# EEZ_DIB_AFE1_r1B5.net
KiCad netlist of a schematic drawn in EAGLE
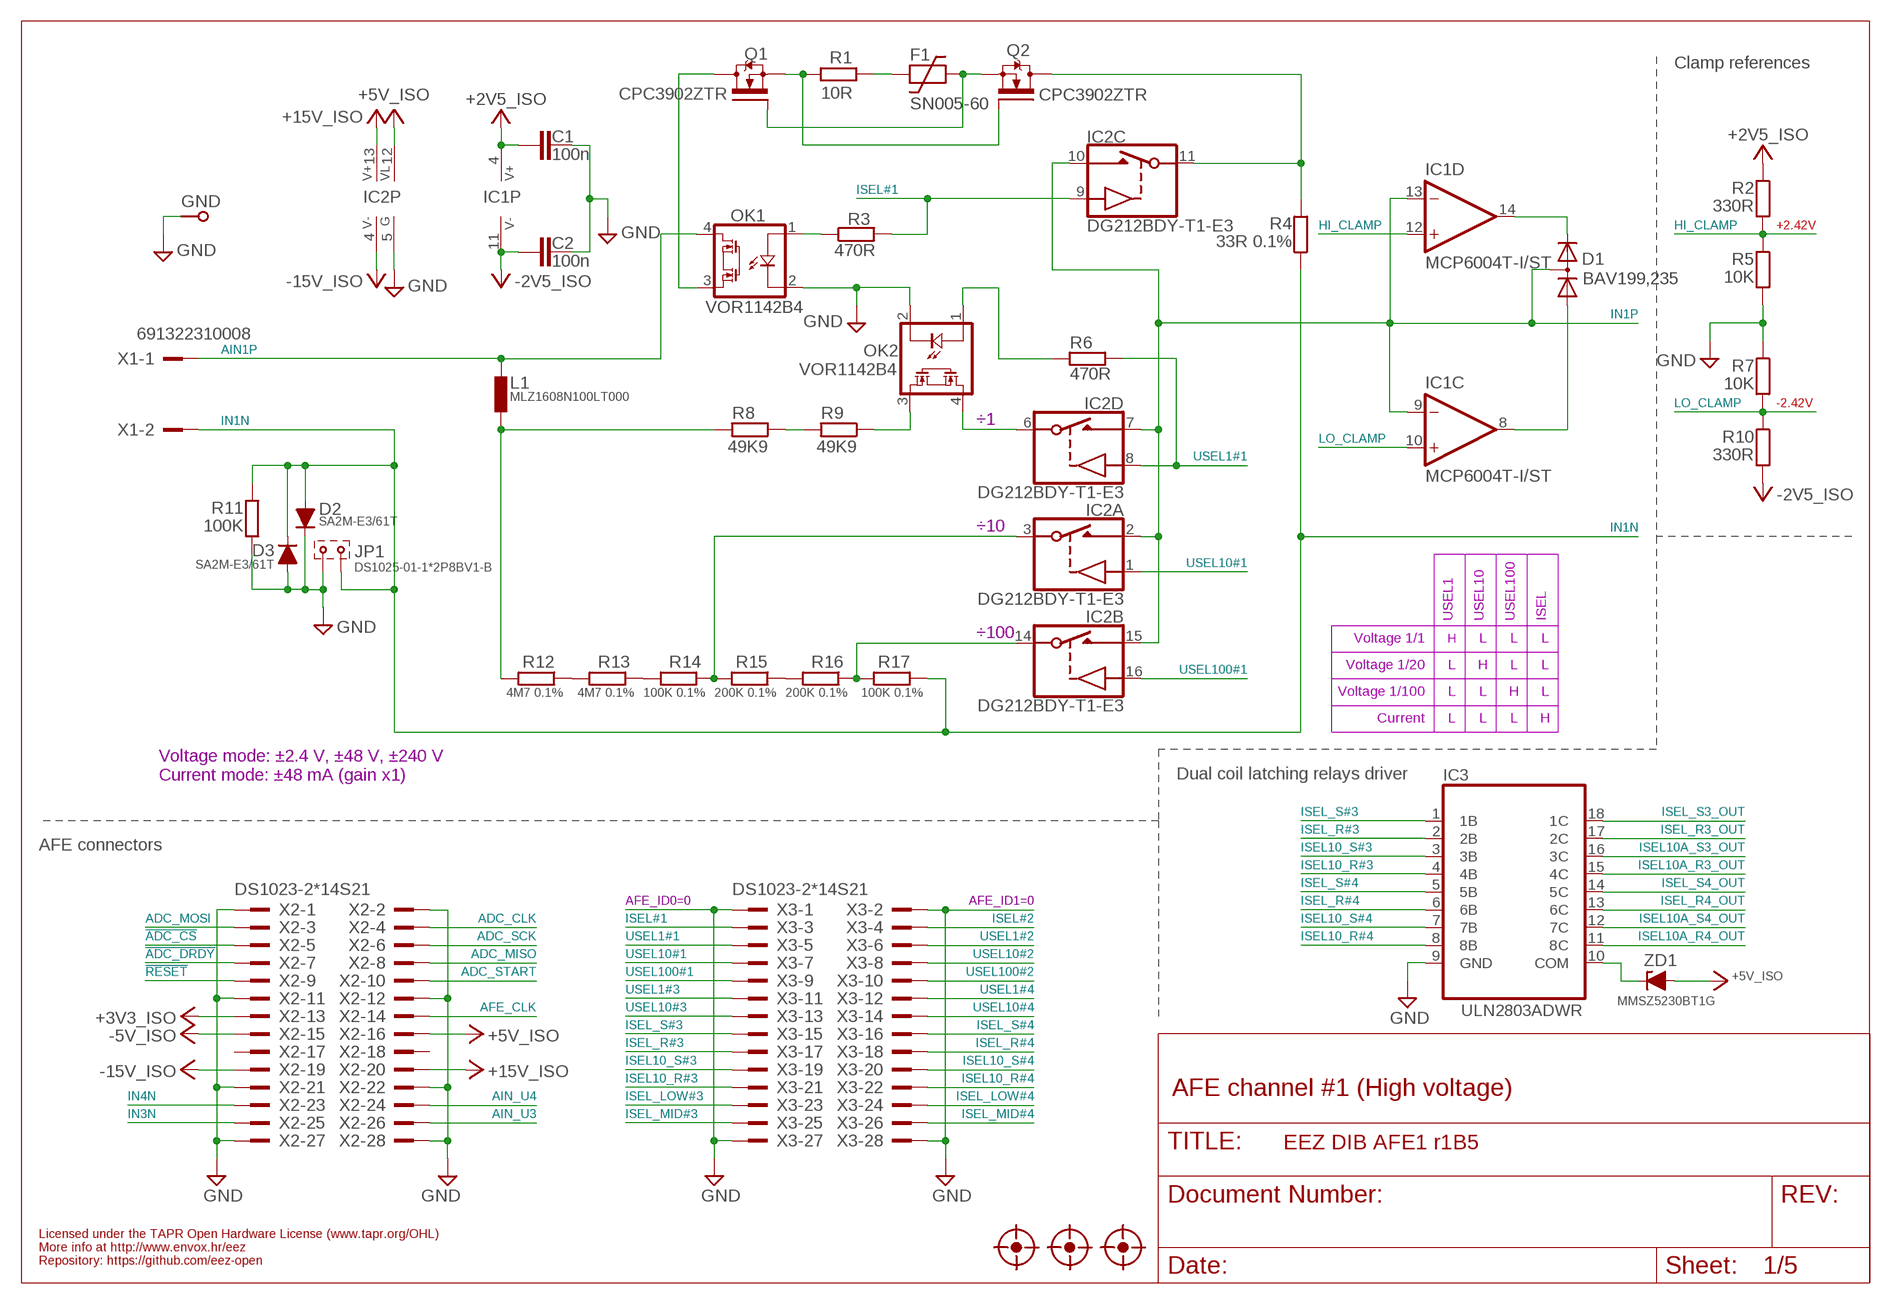
[diagram p0: schematic, sheet 1]
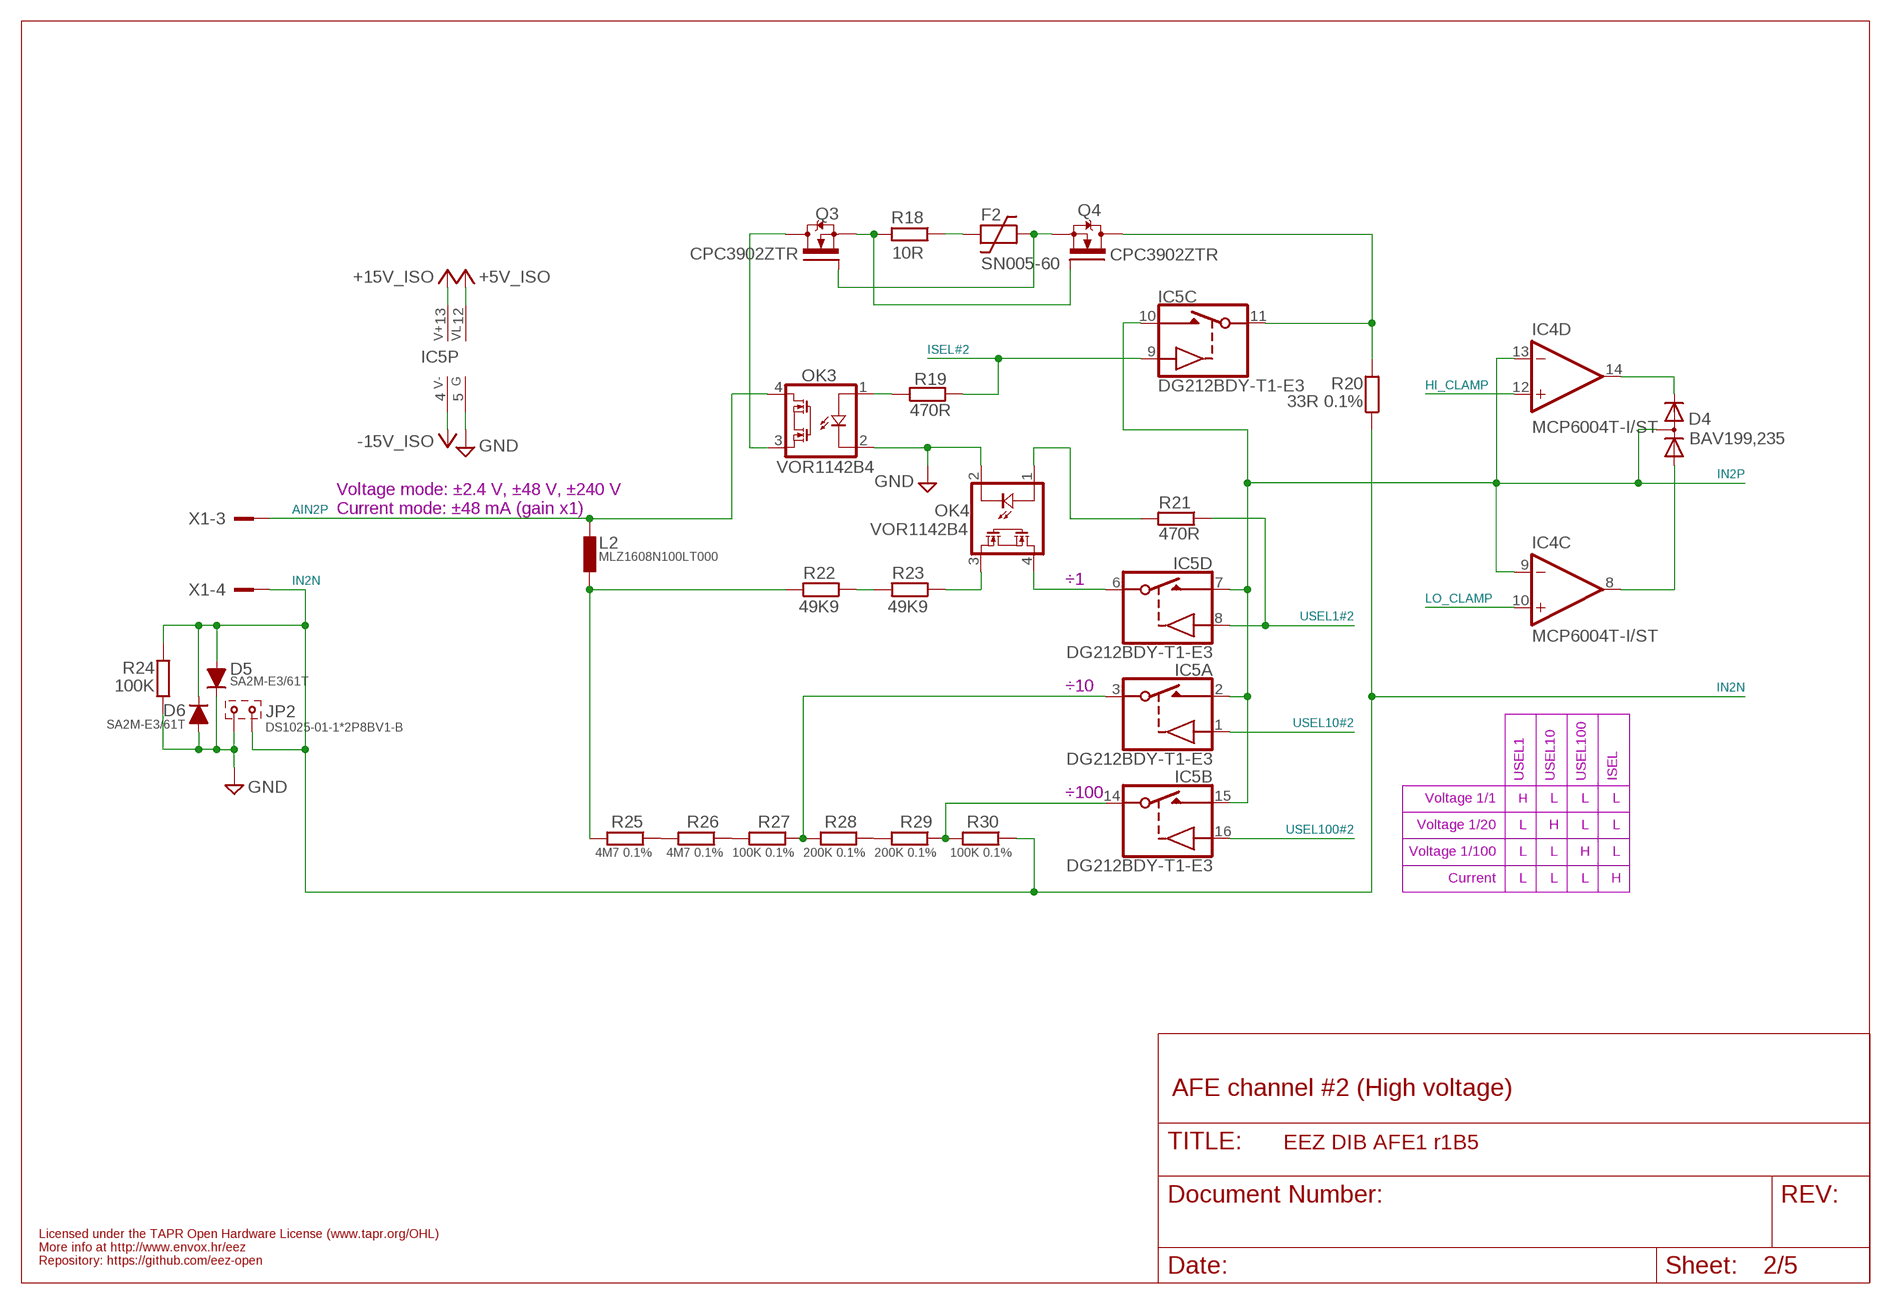
[diagram p1: schematic, sheet 2]
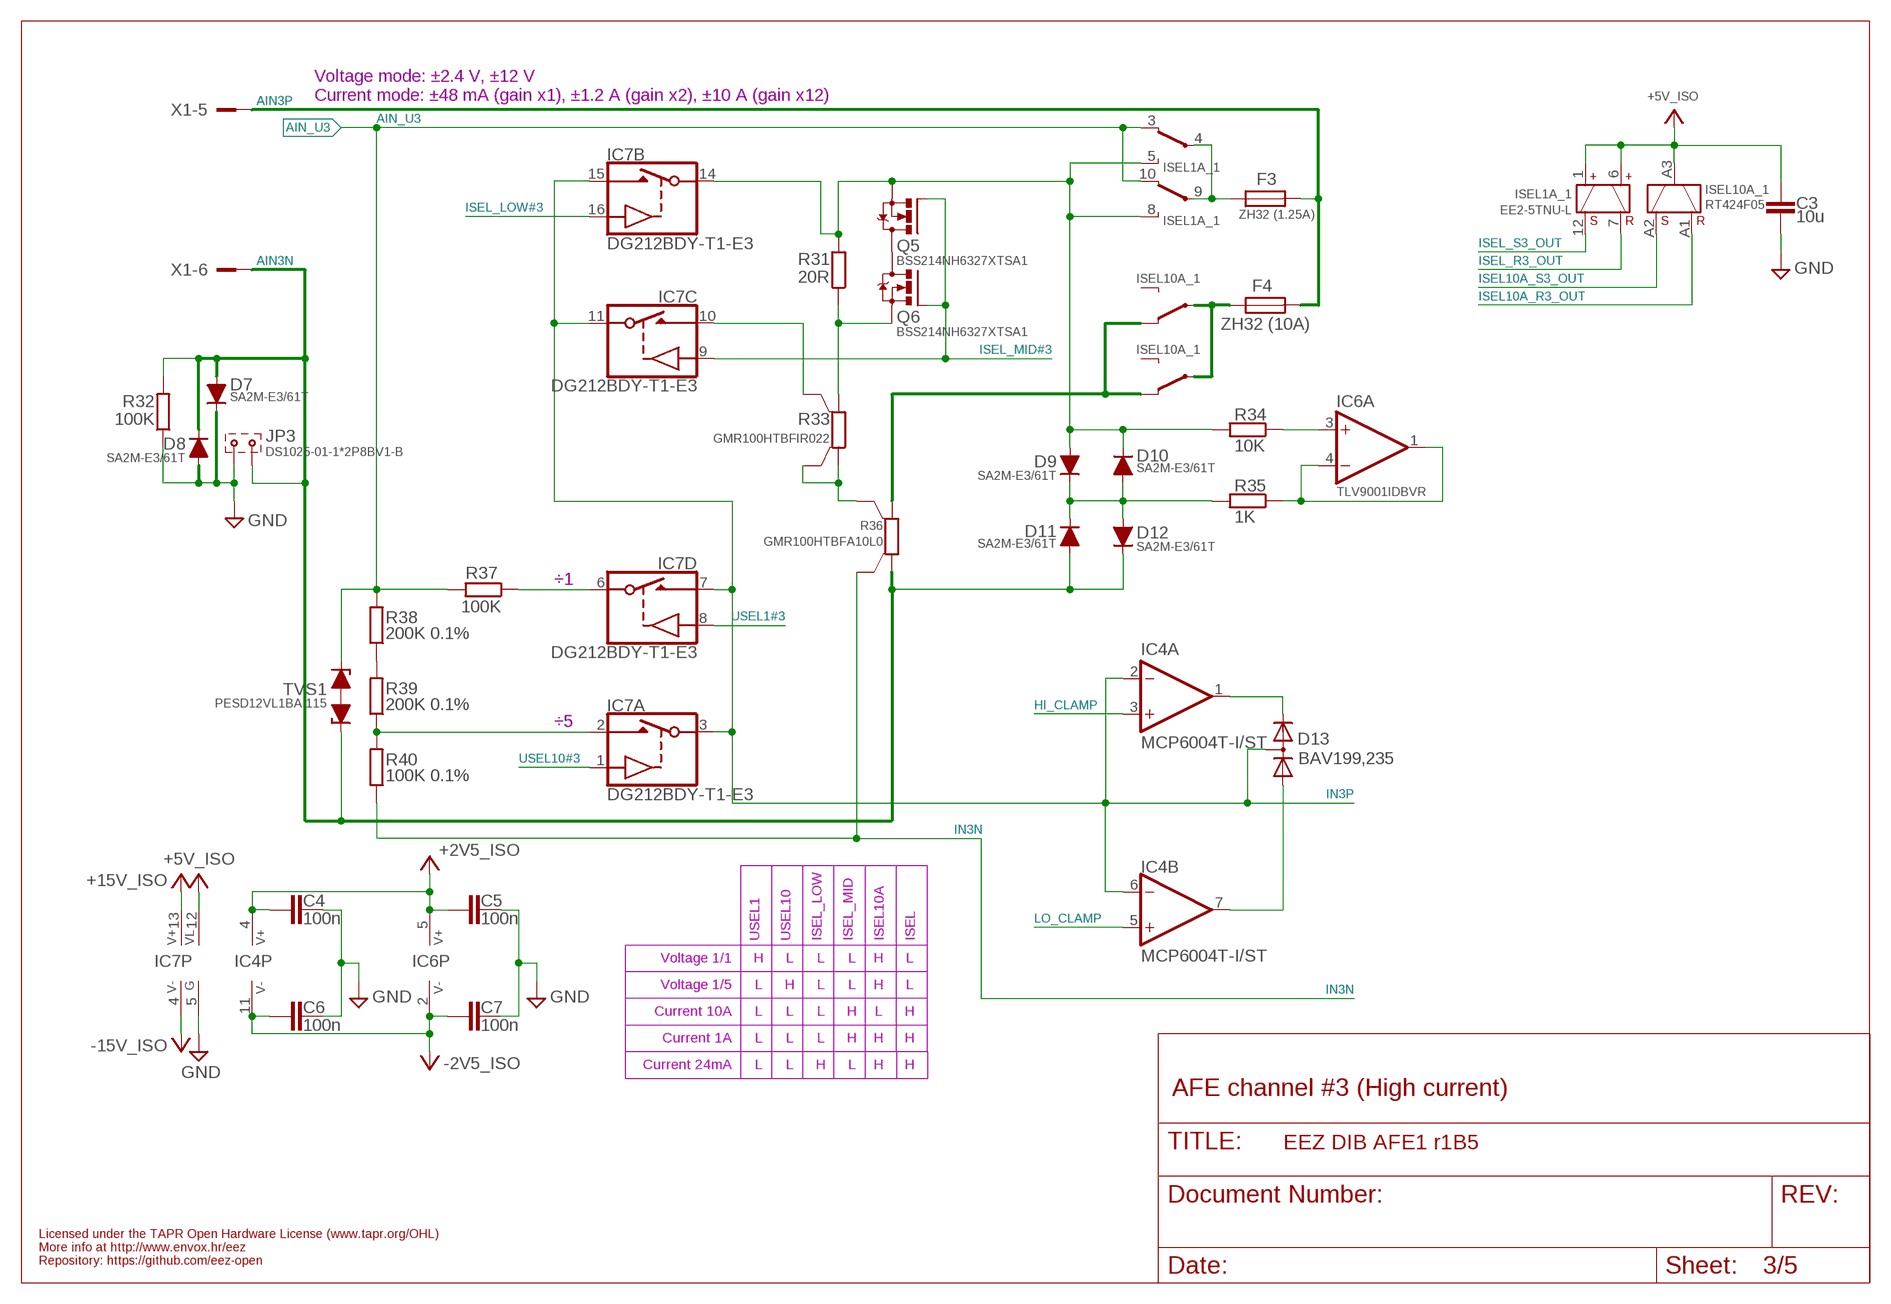
[diagram p2: schematic, sheet 3]
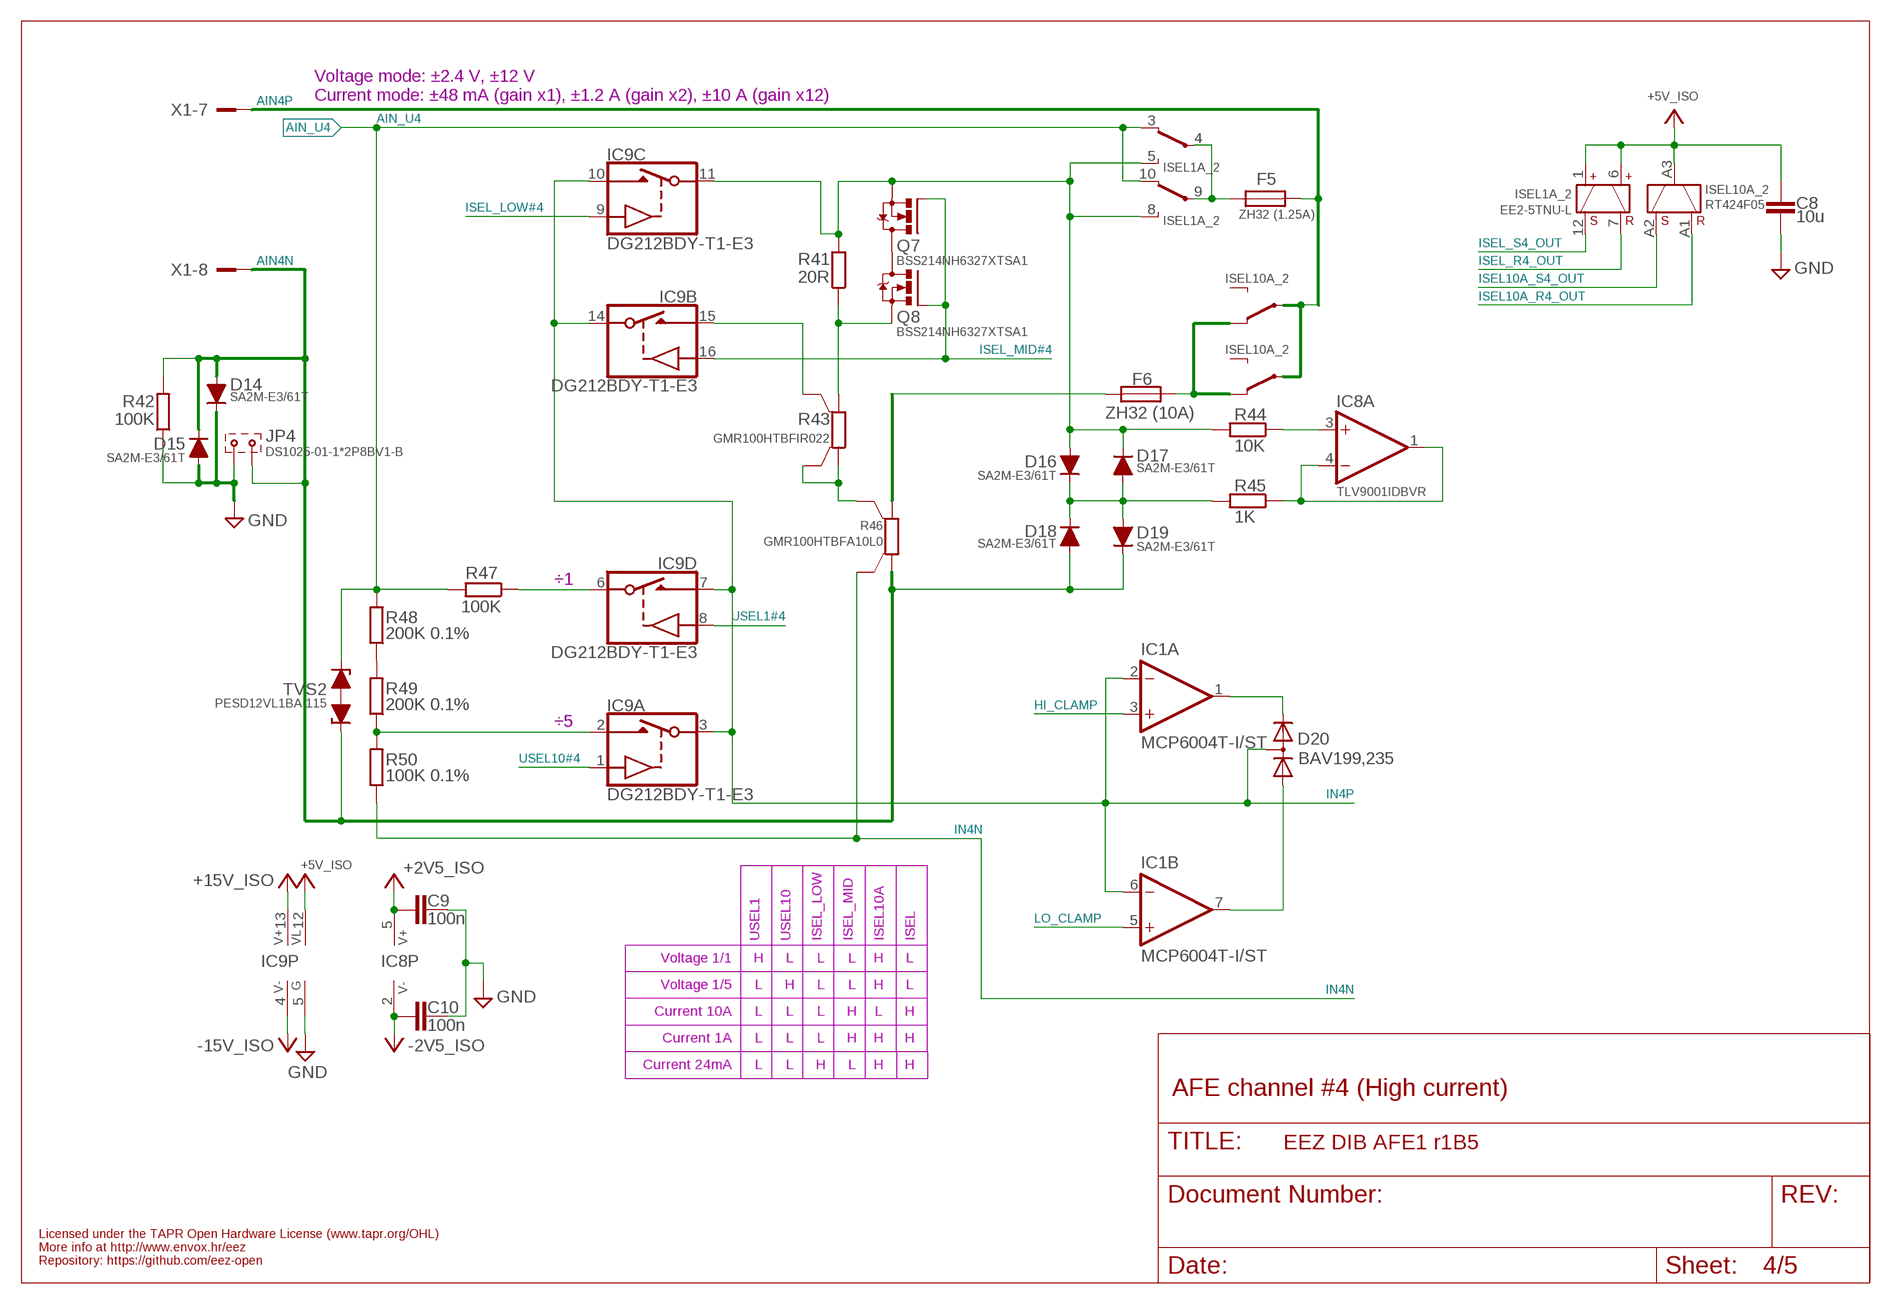
[diagram p3: schematic, sheet 4]
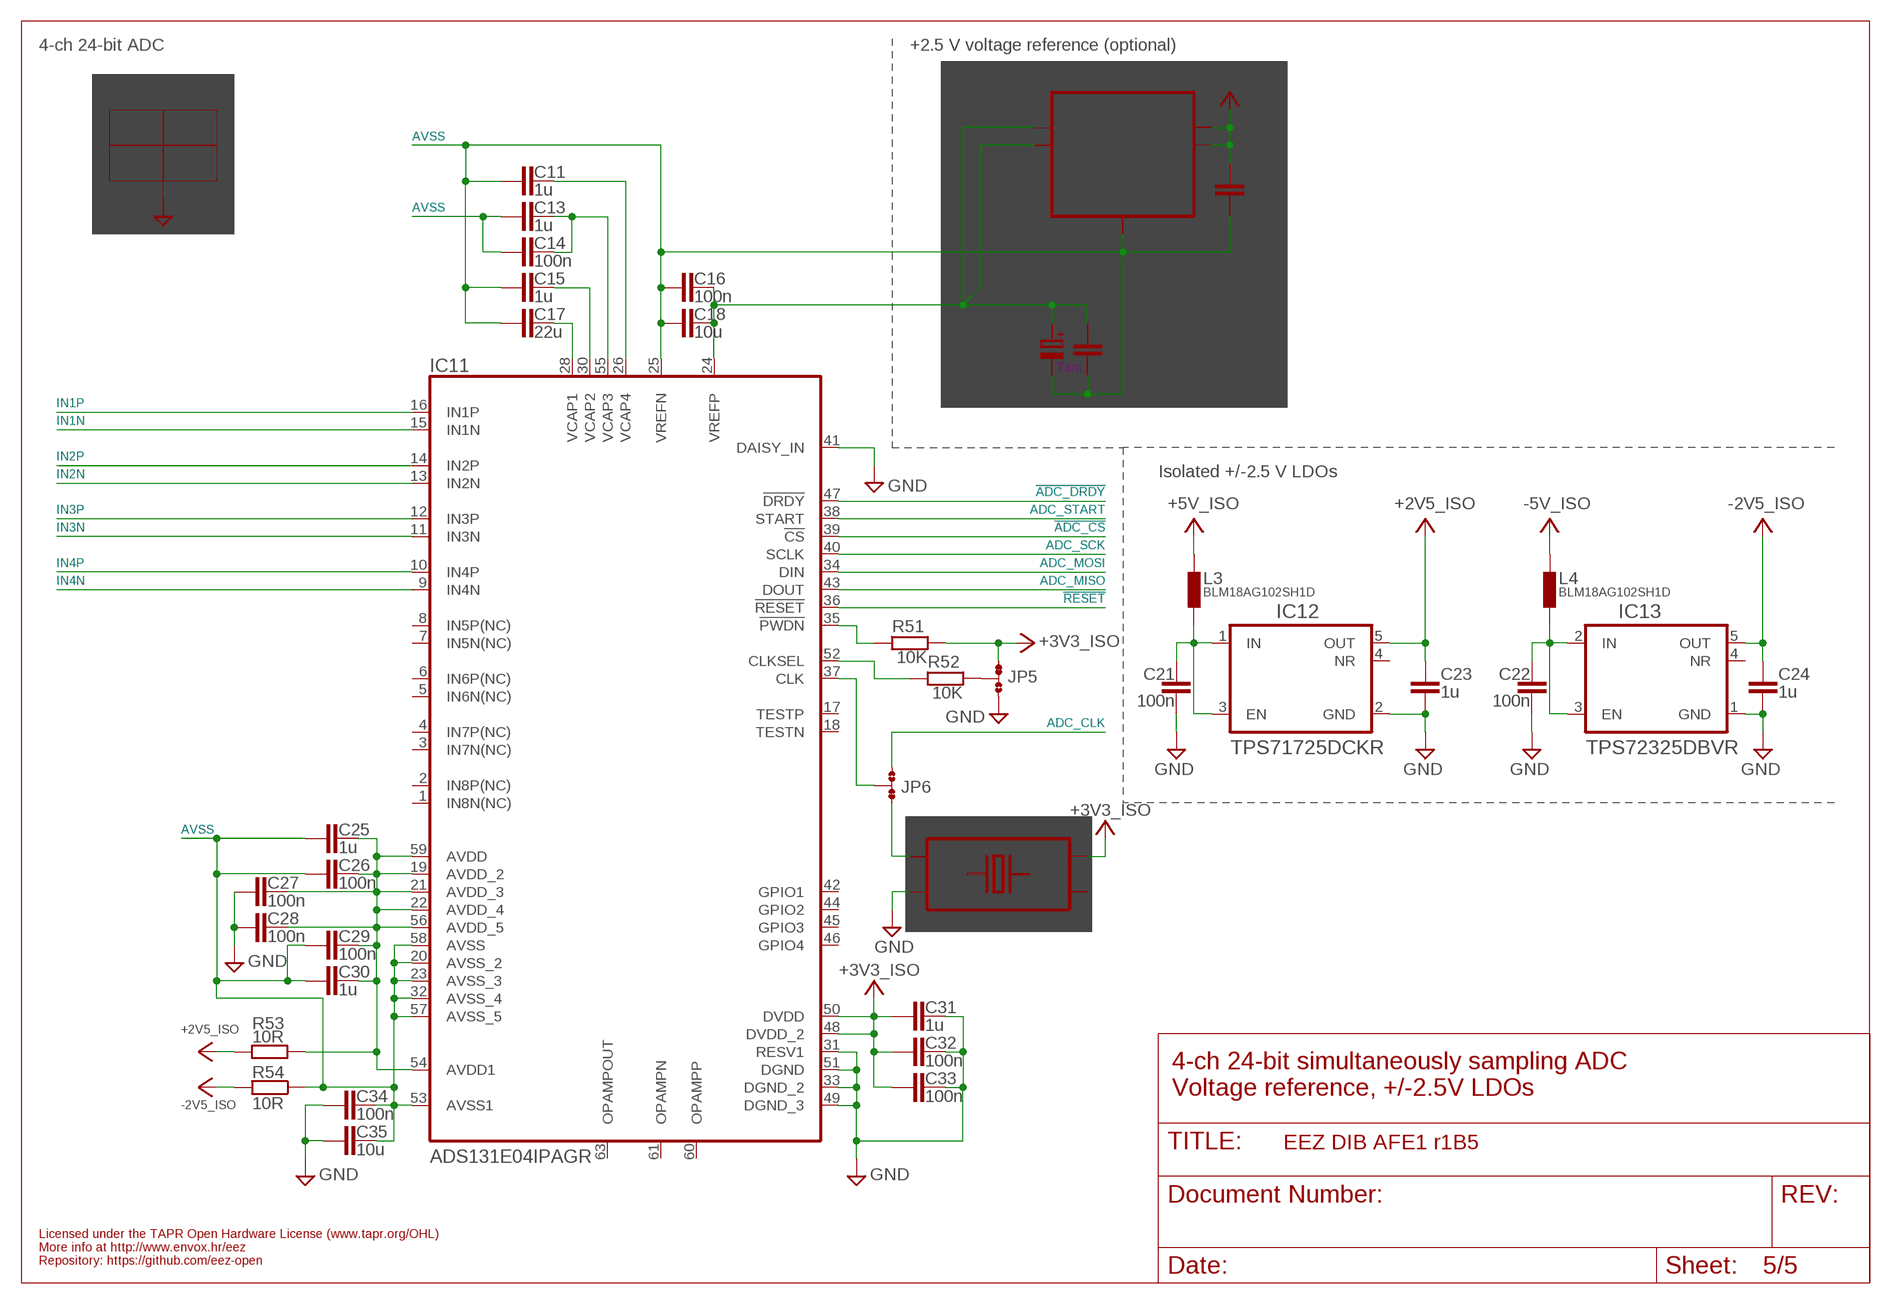
[diagram p4: schematic, sheet 5]

(export (version "E")
  (design (tool "Eeschema 10.0.6"))
  (components
    (comp (ref "D4")
      (value "BAV199,235")
      (footprint "eagle-import:SOT23")
      (libsource (lib "eagle-import") (part "BAV199"))
    )
    (comp (ref "D5")
      (value "SA2M-E3/61T")
      (footprint "eagle-import:SMA_NARROW")
      (libsource (lib "eagle-import") (part "DIODE_SMA-NARROW"))
    )
    (comp (ref "D6")
      (value "SA2M-E3/61T")
      (footprint "eagle-import:SMA_NARROW")
      (libsource (lib "eagle-import") (part "DIODE_SMA-NARROW"))
    )
    (comp (ref "F2")
      (value "SN005-60")
      (footprint "eagle-import:C1206-HV")
      (libsource (lib "eagle-import") (part "FUSE_RESETTABLE2"))
    )
    (comp (ref "IC4")
      (value "MCP6004T-I/ST")
      (footprint "eagle-import:PW(R-PDSO-G14)")
      (libsource (lib "eagle-import") (part "OPA4197PW"))
    )
    (comp (ref "IC5")
      (value "DG212BDY-T1-E3")
      (footprint "eagle-import:SO16")
      (libsource (lib "eagle-import") (part "DG212BDY-T1-E3"))
    )
    (comp (ref "JP2")
      (value "DS1025-01-1*2P8BV1-B")
      (footprint "eagle-import:2MM-2")
      (libsource (lib "eagle-import") (part "JUMPER-2PIN-2MM"))
    )
    (comp (ref "L2")
      (value "MLZ1608N100LT000")
      (footprint "eagle-import:BEAD0603")
      (libsource (lib "eagle-import") (part "FERRITE_BEAD0603"))
    )
    (comp (ref "OK3")
      (value "VOR1142B4")
      (footprint "eagle-import:DIL4-SMD")
      (libsource (lib "eagle-import") (part "VOR1142B4"))
    )
    (comp (ref "OK4")
      (value "VOR1142B4")
      (footprint "eagle-import:DIL4-SMD")
      (libsource (lib "eagle-import") (part "VOR1142B4"))
    )
    (comp (ref "Q3")
      (value "CPC3902ZTR")
      (footprint "eagle-import:SOT230P700X180-4N")
      (libsource (lib "eagle-import") (part "BSP129SOT-223"))
    )
    (comp (ref "Q4")
      (value "CPC3902ZTR")
      (footprint "eagle-import:SOT230P700X180-4N")
      (libsource (lib "eagle-import") (part "BSP129SOT-223"))
    )
    (comp (ref "R18")
      (value "10R")
      (footprint "eagle-import:R0805")
      (libsource (lib "eagle-import") (part "R-EU_R0805"))
    )
    (comp (ref "R19")
      (value "470R")
      (footprint "eagle-import:R0805")
      (libsource (lib "eagle-import") (part "R-EU_R0805"))
    )
    (comp (ref "R20")
      (value "33R 0.1%")
      (footprint "eagle-import:R1206")
      (libsource (lib "eagle-import") (part "R-EU_R1206"))
    )
    (comp (ref "R21")
      (value "470R")
      (footprint "eagle-import:R0805")
      (libsource (lib "eagle-import") (part "R-EU_R0805"))
    )
    (comp (ref "R22")
      (value "49K9")
      (footprint "eagle-import:R1206")
      (libsource (lib "eagle-import") (part "R-EU_R1206"))
    )
    (comp (ref "R23")
      (value "49K9")
      (footprint "eagle-import:R1206")
      (libsource (lib "eagle-import") (part "R-EU_R1206"))
    )
    (comp (ref "R24")
      (value "100K")
      (footprint "eagle-import:R1206")
      (libsource (lib "eagle-import") (part "R-EU_R1206"))
    )
    (comp (ref "R25")
      (value "4M7 0.1%")
      (footprint "eagle-import:R1206")
      (libsource (lib "eagle-import") (part "R-EU_R1206"))
    )
    (comp (ref "R26")
      (value "4M7 0.1%")
      (footprint "eagle-import:R1206")
      (libsource (lib "eagle-import") (part "R-EU_R1206"))
    )
    (comp (ref "R27")
      (value "100K 0.1%")
      (footprint "eagle-import:R1206")
      (libsource (lib "eagle-import") (part "R-EU_R1206"))
    )
    (comp (ref "R28")
      (value "200K 0.1%")
      (footprint "eagle-import:R1206")
      (libsource (lib "eagle-import") (part "R-EU_R1206"))
    )
    (comp (ref "R29")
      (value "200K 0.1%")
      (footprint "eagle-import:R1206")
      (libsource (lib "eagle-import") (part "R-EU_R1206"))
    )
    (comp (ref "R30")
      (value "100K 0.1%")
      (footprint "eagle-import:R1206")
      (libsource (lib "eagle-import") (part "R-EU_R1206"))
    )
    (comp (ref "X1")
      (value "691322310008")
      (footprint "eagle-import:691322310008")
      (libsource (lib "eagle-import") (part "691322310008"))
    )
    (comp (ref "C1")
      (value "100n")
      (footprint "eagle-import:C0603")
      (libsource (lib "eagle-import") (part "C-EUC0603"))
    )
    (comp (ref "C2")
      (value "100n")
      (footprint "eagle-import:C0603")
      (libsource (lib "eagle-import") (part "C-EUC0603"))
    )
    (comp (ref "D1")
      (value "BAV199,235")
      (footprint "eagle-import:SOT23")
      (libsource (lib "eagle-import") (part "BAV199"))
    )
    (comp (ref "D2")
      (value "SA2M-E3/61T")
      (footprint "eagle-import:SMA_NARROW")
      (libsource (lib "eagle-import") (part "DIODE_SMA-NARROW"))
    )
    (comp (ref "D3")
      (value "SA2M-E3/61T")
      (footprint "eagle-import:SMA_NARROW")
      (libsource (lib "eagle-import") (part "DIODE_SMA-NARROW"))
    )
    (comp (ref "F1")
      (value "SN005-60")
      (footprint "eagle-import:C1206-HV")
      (libsource (lib "eagle-import") (part "FUSE_RESETTABLE2"))
    )
    (comp (ref "FM1")
      (value "FIDUCIAL_2")
      (footprint "eagle-import:FIDUCIAL_DUAL")
      (libsource (lib "eagle-import") (part "FIDUCIAL_2"))
    )
    (comp (ref "FM2")
      (value "FIDUCIAL_2")
      (footprint "eagle-import:FIDUCIAL_DUAL")
      (libsource (lib "eagle-import") (part "FIDUCIAL_2"))
    )
    (comp (ref "FM3")
      (value "FIDUCIAL_2")
      (footprint "eagle-import:FIDUCIAL_DUAL")
      (libsource (lib "eagle-import") (part "FIDUCIAL_2"))
    )
    (comp (ref "GND")
      (value "PCB_TEST_TABSHIELD")
      (footprint "eagle-import:PCB_SHIELD_TAB")
      (libsource (lib "eagle-import") (part "PCB_TEST_TABSHIELD"))
    )
    (comp (ref "IC1")
      (value "MCP6004T-I/ST")
      (footprint "eagle-import:PW(R-PDSO-G14)")
      (libsource (lib "eagle-import") (part "OPA4197PW"))
    )
    (comp (ref "IC2")
      (value "DG212BDY-T1-E3")
      (footprint "eagle-import:SO16")
      (libsource (lib "eagle-import") (part "DG212BDY-T1-E3"))
    )
    (comp (ref "IC3")
      (value "ULN2803ADWR")
      (footprint "eagle-import:DW18_TEX-M")
      (libsource (lib "eagle-import") (part "ULN2803ADWR"))
    )
    (comp (ref "JP1")
      (value "DS1025-01-1*2P8BV1-B")
      (footprint "eagle-import:2MM-2")
      (libsource (lib "eagle-import") (part "JUMPER-2PIN-2MM"))
    )
    (comp (ref "L1")
      (value "MLZ1608N100LT000")
      (footprint "eagle-import:BEAD0603")
      (libsource (lib "eagle-import") (part "FERRITE_BEAD0603"))
    )
    (comp (ref "OK1")
      (value "VOR1142B4")
      (footprint "eagle-import:DIL4-SMD")
      (libsource (lib "eagle-import") (part "VOR1142B4"))
    )
    (comp (ref "OK2")
      (value "VOR1142B4")
      (footprint "eagle-import:DIL4-SMD")
      (libsource (lib "eagle-import") (part "VOR1142B4"))
    )
    (comp (ref "Q1")
      (value "CPC3902ZTR")
      (footprint "eagle-import:SOT230P700X180-4N")
      (libsource (lib "eagle-import") (part "BSP129SOT-223"))
    )
    (comp (ref "Q2")
      (value "CPC3902ZTR")
      (footprint "eagle-import:SOT230P700X180-4N")
      (libsource (lib "eagle-import") (part "BSP129SOT-223"))
    )
    (comp (ref "R1")
      (value "10R")
      (footprint "eagle-import:R0805")
      (libsource (lib "eagle-import") (part "R-EU_R0805"))
    )
    (comp (ref "R2")
      (value "330R")
      (footprint "eagle-import:R0805")
      (libsource (lib "eagle-import") (part "R-EU_R0805"))
    )
    (comp (ref "R3")
      (value "470R")
      (footprint "eagle-import:R0805")
      (libsource (lib "eagle-import") (part "R-EU_R0805"))
    )
    (comp (ref "R4")
      (value "33R 0.1%")
      (footprint "eagle-import:R1206")
      (libsource (lib "eagle-import") (part "R-EU_R1206"))
    )
    (comp (ref "R5")
      (value "10K")
      (footprint "eagle-import:R0805")
      (libsource (lib "eagle-import") (part "R-EU_R0805"))
    )
    (comp (ref "R6")
      (value "470R")
      (footprint "eagle-import:R0805")
      (libsource (lib "eagle-import") (part "R-EU_R0805"))
    )
    (comp (ref "R7")
      (value "10K")
      (footprint "eagle-import:R0805")
      (libsource (lib "eagle-import") (part "R-EU_R0805"))
    )
    (comp (ref "R8")
      (value "49K9")
      (footprint "eagle-import:R1206")
      (libsource (lib "eagle-import") (part "R-EU_R1206"))
    )
    (comp (ref "R9")
      (value "49K9")
      (footprint "eagle-import:R1206")
      (libsource (lib "eagle-import") (part "R-EU_R1206"))
    )
    (comp (ref "R10")
      (value "330R")
      (footprint "eagle-import:R0805")
      (libsource (lib "eagle-import") (part "R-EU_R0805"))
    )
    (comp (ref "R11")
      (value "100K")
      (footprint "eagle-import:R1206")
      (libsource (lib "eagle-import") (part "R-EU_R1206"))
    )
    (comp (ref "R12")
      (value "4M7 0.1%")
      (footprint "eagle-import:R1206")
      (libsource (lib "eagle-import") (part "R-EU_R1206"))
    )
    (comp (ref "R13")
      (value "4M7 0.1%")
      (footprint "eagle-import:R1206")
      (libsource (lib "eagle-import") (part "R-EU_R1206"))
    )
    (comp (ref "R14")
      (value "100K 0.1%")
      (footprint "eagle-import:R1206")
      (libsource (lib "eagle-import") (part "R-EU_R1206"))
    )
    (comp (ref "R15")
      (value "200K 0.1%")
      (footprint "eagle-import:R1206")
      (libsource (lib "eagle-import") (part "R-EU_R1206"))
    )
    (comp (ref "R16")
      (value "200K 0.1%")
      (footprint "eagle-import:R1206")
      (libsource (lib "eagle-import") (part "R-EU_R1206"))
    )
    (comp (ref "R17")
      (value "100K 0.1%")
      (footprint "eagle-import:R1206")
      (libsource (lib "eagle-import") (part "R-EU_R1206"))
    )
    (comp (ref "X2")
      (value "DS1023-2*14S21")
      (footprint "eagle-import:TSW-114-07-F-D")
      (libsource (lib "eagle-import") (part "TSW-114-07-F-D"))
    )
    (comp (ref "X3")
      (value "DS1023-2*14S21")
      (footprint "eagle-import:TSW-114-07-F-D")
      (libsource (lib "eagle-import") (part "TSW-114-07-F-D"))
    )
    (comp (ref "ZD1")
      (value "MMSZ5230BT1G")
      (footprint "eagle-import:SOD123")
      (libsource (lib "eagle-import") (part "ZENER-DIODESOD123"))
    )
    (comp (ref "C11")
      (value "1u")
      (footprint "eagle-import:C0805")
      (libsource (lib "eagle-import") (part "C-EUC0805"))
    )
    (comp (ref "C12")
      (value "N.C.")
      (footprint "eagle-import:C1206")
      (libsource (lib "eagle-import") (part "C-EUC1206"))
    )
    (comp (ref "C13")
      (value "1u")
      (footprint "eagle-import:C0805")
      (libsource (lib "eagle-import") (part "C-EUC0805"))
    )
    (comp (ref "C14")
      (value "100n")
      (footprint "eagle-import:C0603")
      (libsource (lib "eagle-import") (part "C-EUC0603"))
    )
    (comp (ref "C15")
      (value "1u")
      (footprint "eagle-import:C0805")
      (libsource (lib "eagle-import") (part "C-EUC0805"))
    )
    (comp (ref "C16")
      (value "100n")
      (footprint "eagle-import:C0603")
      (libsource (lib "eagle-import") (part "C-EUC0603"))
    )
    (comp (ref "C17")
      (value "22u")
      (footprint "eagle-import:C1206")
      (libsource (lib "eagle-import") (part "C-EUC1206"))
    )
    (comp (ref "C18")
      (value "10u")
      (footprint "eagle-import:C1206")
      (libsource (lib "eagle-import") (part "C-EUC1206"))
    )
    (comp (ref "C19")
      (value "N.C.")
      (footprint "eagle-import:EC1206")
      (libsource (lib "eagle-import") (part "ECAP1206"))
    )
    (comp (ref "C20")
      (value "N.C.")
      (footprint "eagle-import:C050-075X110")
      (libsource (lib "eagle-import") (part "C-EU7.5X11"))
    )
    (comp (ref "C21")
      (value "100n")
      (footprint "eagle-import:C0603")
      (libsource (lib "eagle-import") (part "C-EUC0603"))
    )
    (comp (ref "C22")
      (value "100n")
      (footprint "eagle-import:C0603")
      (libsource (lib "eagle-import") (part "C-EUC0603"))
    )
    (comp (ref "C23")
      (value "1u")
      (footprint "eagle-import:C0805")
      (libsource (lib "eagle-import") (part "C-EUC0805"))
    )
    (comp (ref "C24")
      (value "1u")
      (footprint "eagle-import:C0805")
      (libsource (lib "eagle-import") (part "C-EUC0805"))
    )
    (comp (ref "C25")
      (value "1u")
      (footprint "eagle-import:C0805")
      (libsource (lib "eagle-import") (part "C-EUC0805"))
    )
    (comp (ref "C26")
      (value "100n")
      (footprint "eagle-import:C0603")
      (libsource (lib "eagle-import") (part "C-EUC0603"))
    )
    (comp (ref "C27")
      (value "100n")
      (footprint "eagle-import:C0603")
      (libsource (lib "eagle-import") (part "C-EUC0603"))
    )
    (comp (ref "C28")
      (value "100n")
      (footprint "eagle-import:C0603")
      (libsource (lib "eagle-import") (part "C-EUC0603"))
    )
    (comp (ref "C29")
      (value "100n")
      (footprint "eagle-import:C0603")
      (libsource (lib "eagle-import") (part "C-EUC0603"))
    )
    (comp (ref "C30")
      (value "1u")
      (footprint "eagle-import:C0805")
      (libsource (lib "eagle-import") (part "C-EUC0805"))
    )
    (comp (ref "C31")
      (value "1u")
      (footprint "eagle-import:C0805")
      (libsource (lib "eagle-import") (part "C-EUC0805"))
    )
    (comp (ref "C32")
      (value "100n")
      (footprint "eagle-import:C0603")
      (libsource (lib "eagle-import") (part "C-EUC0603"))
    )
    (comp (ref "C33")
      (value "100n")
      (footprint "eagle-import:C0603")
      (libsource (lib "eagle-import") (part "C-EUC0603"))
    )
    (comp (ref "C34")
      (value "100n")
      (footprint "eagle-import:C0603")
      (libsource (lib "eagle-import") (part "C-EUC0603"))
    )
    (comp (ref "C35")
      (value "10u")
      (footprint "eagle-import:C1206")
      (libsource (lib "eagle-import") (part "C-EUC1206"))
    )
    (comp (ref "IC10")
      (value "N.C.")
      (footprint "eagle-import:MSOP-8_MS_LIT")
      (libsource (lib "eagle-import") (part "LTC6655BHMS8"))
    )
    (comp (ref "IC11")
      (value "ADS131E04IPAGR")
      (footprint "eagle-import:PAG64")
      (libsource (lib "eagle-import") (part "ADS131E0XIPAG"))
    )
    (comp (ref "IC12")
      (value "TPS71725DCKR")
      (footprint "eagle-import:DCK5")
      (libsource (lib "eagle-import") (part "TPS71725DCKR"))
    )
    (comp (ref "IC13")
      (value "TPS72325DBVR")
      (footprint "eagle-import:DBV5")
      (libsource (lib "eagle-import") (part "TPS72325DBVR"))
    )
    (comp (ref "JP5")
      (value "JP3-CUT-0805-ROTATED")
      (footprint "eagle-import:JP3-0805-CUT2")
      (libsource (lib "eagle-import") (part "JP3-CUT-0805-ROTATED"))
    )
    (comp (ref "JP6")
      (value "JP3-CUT-0805-ROTATED")
      (footprint "eagle-import:JP3-0805-CUT2")
      (libsource (lib "eagle-import") (part "JP3-CUT-0805-ROTATED"))
    )
    (comp (ref "L3")
      (value "BLM18AG102SH1D")
      (footprint "eagle-import:BEAD0603")
      (libsource (lib "eagle-import") (part "FERRITE_BEAD0603"))
    )
    (comp (ref "L4")
      (value "BLM18AG102SH1D")
      (footprint "eagle-import:BEAD0603")
      (libsource (lib "eagle-import") (part "FERRITE_BEAD0603"))
    )
    (comp (ref "R51")
      (value "10K")
      (footprint "eagle-import:R0805")
      (libsource (lib "eagle-import") (part "R-EU_R0805"))
    )
    (comp (ref "R52")
      (value "10K")
      (footprint "eagle-import:R0805")
      (libsource (lib "eagle-import") (part "R-EU_R0805"))
    )
    (comp (ref "R53")
      (value "10R")
      (footprint "eagle-import:R0805")
      (libsource (lib "eagle-import") (part "R-EU_R0805"))
    )
    (comp (ref "R54")
      (value "10R")
      (footprint "eagle-import:R0805")
      (libsource (lib "eagle-import") (part "R-EU_R0805"))
    )
    (comp (ref "S1")
      (value "N.C.")
      (footprint "eagle-import:2118732-2")
      (libsource (lib "eagle-import") (part "2118732-2"))
    )
    (comp (ref "XO1")
      (value "N.C.")
      (footprint "eagle-import:XLH")
      (libsource (lib "eagle-import") (part "XLH"))
    )
    (comp (ref "C3")
      (value "10u")
      (footprint "eagle-import:C1206")
      (libsource (lib "eagle-import") (part "C-EUC1206"))
    )
    (comp (ref "C4")
      (value "100n")
      (footprint "eagle-import:C0603")
      (libsource (lib "eagle-import") (part "C-EUC0603"))
    )
    (comp (ref "C5")
      (value "100n")
      (footprint "eagle-import:C0603")
      (libsource (lib "eagle-import") (part "C-EUC0603"))
    )
    (comp (ref "C6")
      (value "100n")
      (footprint "eagle-import:C0603")
      (libsource (lib "eagle-import") (part "C-EUC0603"))
    )
    (comp (ref "C7")
      (value "100n")
      (footprint "eagle-import:C0603")
      (libsource (lib "eagle-import") (part "C-EUC0603"))
    )
    (comp (ref "D7")
      (value "SA2M-E3/61T")
      (footprint "eagle-import:SMA_NARROW")
      (libsource (lib "eagle-import") (part "DIODE_SMA-NARROW"))
    )
    (comp (ref "D8")
      (value "SA2M-E3/61T")
      (footprint "eagle-import:SMA_NARROW")
      (libsource (lib "eagle-import") (part "DIODE_SMA-NARROW"))
    )
    (comp (ref "D9")
      (value "SA2M-E3/61T")
      (footprint "eagle-import:SMA_NARROW")
      (libsource (lib "eagle-import") (part "DIODE_SMA-NARROW"))
    )
    (comp (ref "D10")
      (value "SA2M-E3/61T")
      (footprint "eagle-import:SMA_NARROW")
      (libsource (lib "eagle-import") (part "DIODE_SMA-NARROW"))
    )
    (comp (ref "D11")
      (value "SA2M-E3/61T")
      (footprint "eagle-import:SMA_NARROW")
      (libsource (lib "eagle-import") (part "DIODE_SMA-NARROW"))
    )
    (comp (ref "D12")
      (value "SA2M-E3/61T")
      (footprint "eagle-import:SMA_NARROW")
      (libsource (lib "eagle-import") (part "DIODE_SMA-NARROW"))
    )
    (comp (ref "D13")
      (value "BAV199,235")
      (footprint "eagle-import:SOT23")
      (libsource (lib "eagle-import") (part "BAV199"))
    )
    (comp (ref "F3")
      (value "ZH32 (1.25A)")
      (footprint "eagle-import:ZH32")
      (libsource (lib "eagle-import") (part "ZH32"))
    )
    (comp (ref "F4")
      (value "ZH32 (10A)")
      (footprint "eagle-import:ZH32")
      (libsource (lib "eagle-import") (part "ZH32"))
    )
    (comp (ref "IC6")
      (value "TLV9001IDBVR")
      (footprint "eagle-import:DBV5")
      (libsource (lib "eagle-import") (part "OPA376AIDBVR"))
    )
    (comp (ref "IC7")
      (value "DG212BDY-T1-E3")
      (footprint "eagle-import:SO16")
      (libsource (lib "eagle-import") (part "DG212BDY-T1-E3"))
    )
    (comp (ref "ISEL1A_1")
      (value "EE2-5TNU-L")
      (footprint "eagle-import:G6SK-2F")
      (libsource (lib "eagle-import") (part "G6SK-2F"))
    )
    (comp (ref "ISEL10A_1")
      (value "RT424F05")
      (footprint "eagle-import:RT424FXX")
      (libsource (lib "eagle-import") (part "RT424FXX"))
    )
    (comp (ref "JP3")
      (value "DS1025-01-1*2P8BV1-B")
      (footprint "eagle-import:2MM-2")
      (libsource (lib "eagle-import") (part "JUMPER-2PIN-2MM"))
    )
    (comp (ref "Q5")
      (value "BSS214NH6327XTSA1")
      (footprint "eagle-import:SOT103P240X110-3N")
      (fields
        (field (name "MPN") "2N7002-7-F")
        (field (name "MPN_1") "2N7002-7-F")
        (field (name "OC_FARNELL") "1713823")
        (field (name "OC_NEWARK") "25R5679")
        (field (name "PACKAGE") "SOT-23-3")
        (field (name "SUPPLIER") "DIODES INC.")
      )
      (libsource (lib "eagle-import") (part "2N7002"))
    )
    (comp (ref "Q6")
      (value "BSS214NH6327XTSA1")
      (footprint "eagle-import:SOT103P240X110-3N")
      (fields (field (name "MPN") "2N7002-7-F"))
      (libsource (lib "eagle-import") (part "2N7002"))
    )
    (comp (ref "R31")
      (value "20R")
      (footprint "eagle-import:R1206")
      (libsource (lib "eagle-import") (part "R-EU_R1206"))
    )
    (comp (ref "R32")
      (value "100K")
      (footprint "eagle-import:R1206")
      (libsource (lib "eagle-import") (part "R-EU_R1206"))
    )
    (comp (ref "R33")
      (value "GMR100HTBFIR022")
      (footprint "eagle-import:R_2512-4WIRE")
      (libsource (lib "eagle-import") (part "R-EU_4WIRE2512"))
    )
    (comp (ref "R34")
      (value "10K")
      (footprint "eagle-import:R0805")
      (libsource (lib "eagle-import") (part "R-EU_R0805"))
    )
    (comp (ref "R35")
      (value "1K")
      (footprint "eagle-import:R0805")
      (libsource (lib "eagle-import") (part "R-EU_R0805"))
    )
    (comp (ref "R36")
      (value "GMR100HTBFA10L0")
      (footprint "eagle-import:R_2512-4WIRE")
      (libsource (lib "eagle-import") (part "R-EU_4WIRE2512"))
    )
    (comp (ref "R37")
      (value "100K")
      (footprint "eagle-import:R1206")
      (libsource (lib "eagle-import") (part "R-EU_R1206"))
    )
    (comp (ref "R38")
      (value "200K 0.1%")
      (footprint "eagle-import:R1206")
      (libsource (lib "eagle-import") (part "R-EU_R1206"))
    )
    (comp (ref "R39")
      (value "200K 0.1%")
      (footprint "eagle-import:R1206")
      (libsource (lib "eagle-import") (part "R-EU_R1206"))
    )
    (comp (ref "R40")
      (value "100K 0.1%")
      (footprint "eagle-import:R1206")
      (libsource (lib "eagle-import") (part "R-EU_R1206"))
    )
    (comp (ref "TVS1")
      (value "PESD12VL1BA,115")
      (footprint "eagle-import:SOD323-BIDIR")
      (libsource (lib "eagle-import") (part "PESDXL1BA"))
    )
    (comp (ref "C8")
      (value "10u")
      (footprint "eagle-import:C1206")
      (libsource (lib "eagle-import") (part "C-EUC1206"))
    )
    (comp (ref "C9")
      (value "100n")
      (footprint "eagle-import:C0603")
      (libsource (lib "eagle-import") (part "C-EUC0603"))
    )
    (comp (ref "C10")
      (value "100n")
      (footprint "eagle-import:C0603")
      (libsource (lib "eagle-import") (part "C-EUC0603"))
    )
    (comp (ref "D14")
      (value "SA2M-E3/61T")
      (footprint "eagle-import:SMA_NARROW")
      (libsource (lib "eagle-import") (part "DIODE_SMA-NARROW"))
    )
    (comp (ref "D15")
      (value "SA2M-E3/61T")
      (footprint "eagle-import:SMA_NARROW")
      (libsource (lib "eagle-import") (part "DIODE_SMA-NARROW"))
    )
    (comp (ref "D16")
      (value "SA2M-E3/61T")
      (footprint "eagle-import:SMA_NARROW")
      (libsource (lib "eagle-import") (part "DIODE_SMA-NARROW"))
    )
    (comp (ref "D17")
      (value "SA2M-E3/61T")
      (footprint "eagle-import:SMA_NARROW")
      (libsource (lib "eagle-import") (part "DIODE_SMA-NARROW"))
    )
    (comp (ref "D18")
      (value "SA2M-E3/61T")
      (footprint "eagle-import:SMA_NARROW")
      (libsource (lib "eagle-import") (part "DIODE_SMA-NARROW"))
    )
    (comp (ref "D19")
      (value "SA2M-E3/61T")
      (footprint "eagle-import:SMA_NARROW")
      (libsource (lib "eagle-import") (part "DIODE_SMA-NARROW"))
    )
    (comp (ref "D20")
      (value "BAV199,235")
      (footprint "eagle-import:SOT23")
      (libsource (lib "eagle-import") (part "BAV199"))
    )
    (comp (ref "F5")
      (value "ZH32 (1.25A)")
      (footprint "eagle-import:ZH32")
      (libsource (lib "eagle-import") (part "ZH32"))
    )
    (comp (ref "F6")
      (value "ZH32 (10A)")
      (footprint "eagle-import:ZH32")
      (libsource (lib "eagle-import") (part "ZH32"))
    )
    (comp (ref "IC8")
      (value "TLV9001IDBVR")
      (footprint "eagle-import:DBV5")
      (libsource (lib "eagle-import") (part "OPA376AIDBVR"))
    )
    (comp (ref "IC9")
      (value "DG212BDY-T1-E3")
      (footprint "eagle-import:SO16")
      (libsource (lib "eagle-import") (part "DG212BDY-T1-E3"))
    )
    (comp (ref "ISEL1A_2")
      (value "EE2-5TNU-L")
      (footprint "eagle-import:G6SK-2F")
      (libsource (lib "eagle-import") (part "G6SK-2F"))
    )
    (comp (ref "ISEL10A_2")
      (value "RT424F05")
      (footprint "eagle-import:RT424FXX")
      (libsource (lib "eagle-import") (part "RT424FXX"))
    )
    (comp (ref "JP4")
      (value "DS1025-01-1*2P8BV1-B")
      (footprint "eagle-import:2MM-2")
      (libsource (lib "eagle-import") (part "JUMPER-2PIN-2MM"))
    )
    (comp (ref "Q7")
      (value "BSS214NH6327XTSA1")
      (footprint "eagle-import:SOT103P240X110-3N")
      (fields
        (field (name "MPN") "2N7002-7-F")
        (field (name "MPN_1") "2N7002-7-F")
        (field (name "OC_FARNELL") "1713823")
        (field (name "OC_NEWARK") "25R5679")
        (field (name "PACKAGE") "SOT-23-3")
        (field (name "SUPPLIER") "DIODES INC.")
      )
      (libsource (lib "eagle-import") (part "2N7002"))
    )
    (comp (ref "Q8")
      (value "BSS214NH6327XTSA1")
      (footprint "eagle-import:SOT103P240X110-3N")
      (fields (field (name "MPN") "2N7002-7-F"))
      (libsource (lib "eagle-import") (part "2N7002"))
    )
    (comp (ref "R41")
      (value "20R")
      (footprint "eagle-import:R1206")
      (libsource (lib "eagle-import") (part "R-EU_R1206"))
    )
    (comp (ref "R42")
      (value "100K")
      (footprint "eagle-import:R1206")
      (libsource (lib "eagle-import") (part "R-EU_R1206"))
    )
    (comp (ref "R43")
      (value "GMR100HTBFIR022")
      (footprint "eagle-import:R_2512-4WIRE")
      (libsource (lib "eagle-import") (part "R-EU_4WIRE2512"))
    )
    (comp (ref "R44")
      (value "10K")
      (footprint "eagle-import:R0805")
      (libsource (lib "eagle-import") (part "R-EU_R0805"))
    )
    (comp (ref "R45")
      (value "1K")
      (footprint "eagle-import:R0805")
      (libsource (lib "eagle-import") (part "R-EU_R0805"))
    )
    (comp (ref "R46")
      (value "GMR100HTBFA10L0")
      (footprint "eagle-import:R_2512-4WIRE")
      (libsource (lib "eagle-import") (part "R-EU_4WIRE2512"))
    )
    (comp (ref "R47")
      (value "100K")
      (footprint "eagle-import:R1206")
      (libsource (lib "eagle-import") (part "R-EU_R1206"))
    )
    (comp (ref "R48")
      (value "200K 0.1%")
      (footprint "eagle-import:R1206")
      (libsource (lib "eagle-import") (part "R-EU_R1206"))
    )
    (comp (ref "R49")
      (value "200K 0.1%")
      (footprint "eagle-import:R1206")
      (libsource (lib "eagle-import") (part "R-EU_R1206"))
    )
    (comp (ref "R50")
      (value "100K 0.1%")
      (footprint "eagle-import:R1206")
      (libsource (lib "eagle-import") (part "R-EU_R1206"))
    )
    (comp (ref "TVS2")
      (value "PESD12VL1BA,115")
      (footprint "eagle-import:SOD323-BIDIR")
      (libsource (lib "eagle-import") (part "PESDXL1BA"))
    )
  )
  (nets
    (net (code "1") (name "+2V5_ISO") (class "Default")
      (node (ref "C1") (pin "2") (pinfunction "2_2") (pintype "passive"))
      (node (ref "C23") (pin "2") (pinfunction "2_2") (pintype "passive"))
      (node (ref "C4") (pin "2") (pinfunction "2_2") (pintype "passive"))
      (node (ref "C5") (pin "2") (pinfunction "2_2") (pintype "passive"))
      (node (ref "C9") (pin "2") (pinfunction "2_2") (pintype "passive"))
      (node (ref "IC1") (pin "4") (pinfunction "V+_4") (pintype "power_in"))
      (node (ref "IC12") (pin "5") (pinfunction "OUT_5") (pintype "passive"))
      (node (ref "IC4") (pin "4") (pinfunction "V+_4") (pintype "power_in"))
      (node (ref "IC6") (pin "5") (pinfunction "V+_5") (pintype "power_in"))
      (node (ref "IC8") (pin "5") (pinfunction "V+_5") (pintype "power_in"))
      (node (ref "R2") (pin "1") (pinfunction "1_1") (pintype "passive"))
      (node (ref "R53") (pin "1") (pinfunction "1_1") (pintype "passive"))
    )
    (net (code "2") (name "+3V3_ISO") (class "Default")
      (node (ref "C31") (pin "1") (pinfunction "1_1") (pintype "passive"))
      (node (ref "C32") (pin "2") (pinfunction "2_2") (pintype "passive"))
      (node (ref "C33") (pin "2") (pinfunction "2_2") (pintype "passive"))
      (node (ref "IC11") (pin "48") (pinfunction "DVDD_2_48") (pintype "power_in"))
      (node (ref "IC11") (pin "50") (pinfunction "DVDD_50") (pintype "power_in"))
      (node (ref "JP5") (pin "NC") (pinfunction "NC_NC") (pintype "passive"))
      (node (ref "R51") (pin "2") (pinfunction "2_2") (pintype "passive"))
      (node (ref "X2") (pin "13") (pinfunction "1_13") (pintype "passive"))
      (node (ref "XO1") (pin "6") (pinfunction "VDD_6") (pintype "power_in"))
    )
    (net (code "3") (name "+5V_ISO") (class "Default")
      (node (ref "C12") (pin "1") (pinfunction "1_1") (pintype "passive"))
      (node (ref "C3") (pin "1") (pinfunction "1_1") (pintype "passive"))
      (node (ref "C8") (pin "1") (pinfunction "1_1") (pintype "passive"))
      (node (ref "IC10") (pin "1") (pinfunction "~{SHDN}_1") (pintype "input"))
      (node (ref "IC10") (pin "2") (pinfunction "VIN_2") (pintype "input"))
      (node (ref "IC2") (pin "12") (pinfunction "VL_12") (pintype "power_in"))
      (node (ref "IC5") (pin "12") (pinfunction "VL_12") (pintype "power_in"))
      (node (ref "IC7") (pin "12") (pinfunction "VL_12") (pintype "power_in"))
      (node (ref "IC9") (pin "12") (pinfunction "VL_12") (pintype "power_in"))
      (node (ref "ISEL10A_1") (pin "A3") (pinfunction "COM_A3") (pintype "passive"))
      (node (ref "ISEL10A_2") (pin "A3") (pinfunction "COM_A3") (pintype "passive"))
      (node (ref "ISEL1A_1") (pin "1") (pinfunction "S+_1") (pintype "passive"))
      (node (ref "ISEL1A_1") (pin "6") (pinfunction "R+_6") (pintype "passive"))
      (node (ref "ISEL1A_2") (pin "1") (pinfunction "S+_1") (pintype "passive"))
      (node (ref "ISEL1A_2") (pin "6") (pinfunction "R+_6") (pintype "passive"))
      (node (ref "L3") (pin "P$2") (pinfunction "2_P$2") (pintype "passive"))
      (node (ref "X2") (pin "16") (pinfunction "1_16") (pintype "passive"))
      (node (ref "ZD1") (pin "A") (pinfunction "A_A") (pintype "passive"))
    )
    (net (code "4") (name "+15V_ISO") (class "Default")
      (node (ref "IC2") (pin "13") (pinfunction "V+_13") (pintype "power_in"))
      (node (ref "IC5") (pin "13") (pinfunction "V+_13") (pintype "power_in"))
      (node (ref "IC7") (pin "13") (pinfunction "V+_13") (pintype "power_in"))
      (node (ref "IC9") (pin "13") (pinfunction "V+_13") (pintype "power_in"))
      (node (ref "X2") (pin "20") (pinfunction "1_20") (pintype "passive"))
    )
    (net (code "5") (name "-2V5_ISO") (class "Default")
      (node (ref "C10") (pin "2") (pinfunction "2_2") (pintype "passive"))
      (node (ref "C2") (pin "2") (pinfunction "2_2") (pintype "passive"))
      (node (ref "C24") (pin "2") (pinfunction "2_2") (pintype "passive"))
      (node (ref "C6") (pin "2") (pinfunction "2_2") (pintype "passive"))
      (node (ref "C7") (pin "2") (pinfunction "2_2") (pintype "passive"))
      (node (ref "IC1") (pin "11") (pinfunction "V-_11") (pintype "power_in"))
      (node (ref "IC13") (pin "5") (pinfunction "OUT_5") (pintype "passive"))
      (node (ref "IC4") (pin "11") (pinfunction "V-_11") (pintype "power_in"))
      (node (ref "IC6") (pin "2") (pinfunction "V-_2") (pintype "power_in"))
      (node (ref "IC8") (pin "2") (pinfunction "V-_2") (pintype "power_in"))
      (node (ref "R10") (pin "2") (pinfunction "2_2") (pintype "passive"))
      (node (ref "R54") (pin "2") (pinfunction "2_2") (pintype "passive"))
    )
    (net (code "6") (name "-5V_ISO") (class "Default")
      (node (ref "L4") (pin "P$2") (pinfunction "2_P$2") (pintype "passive"))
      (node (ref "X2") (pin "15") (pinfunction "1_15") (pintype "passive"))
    )
    (net (code "7") (name "-15V_ISO") (class "Default")
      (node (ref "IC2") (pin "4") (pinfunction "V-_4") (pintype "power_in"))
      (node (ref "IC5") (pin "4") (pinfunction "V-_4") (pintype "power_in"))
      (node (ref "IC7") (pin "4") (pinfunction "V-_4") (pintype "power_in"))
      (node (ref "IC9") (pin "4") (pinfunction "V-_4") (pintype "power_in"))
      (node (ref "X2") (pin "19") (pinfunction "1_19") (pintype "passive"))
    )
    (net (code "8") (name "ADC_CLK") (class "Default")
      (node (ref "JP6") (pin "NO") (pinfunction "NO_NO") (pintype "passive"))
      (node (ref "X2") (pin "4") (pinfunction "1_4") (pintype "passive"))
    )
    (net (code "9") (name "ADC_MISO") (class "Default")
      (node (ref "IC11") (pin "43") (pinfunction "DOUT_43") (pintype "output"))
      (node (ref "X2") (pin "8") (pinfunction "1_8") (pintype "passive"))
    )
    (net (code "10") (name "ADC_MOSI") (class "Default")
      (node (ref "IC11") (pin "34") (pinfunction "DIN_34") (pintype "input"))
      (node (ref "X2") (pin "3") (pinfunction "1_3") (pintype "passive"))
    )
    (net (code "11") (name "ADC_SCK") (class "Default")
      (node (ref "IC11") (pin "40") (pinfunction "SCLK_40") (pintype "input"))
      (node (ref "X2") (pin "6") (pinfunction "1_6") (pintype "passive"))
    )
    (net (code "12") (name "ADC_START") (class "Default")
      (node (ref "IC11") (pin "38") (pinfunction "START_38") (pintype "input"))
      (node (ref "X2") (pin "10") (pinfunction "1_10") (pintype "passive"))
    )
    (net (code "13") (name "AFE_CLK") (class "Default")
      (node (ref "X2") (pin "14") (pinfunction "1_14") (pintype "passive"))
    )
    (net (code "14") (name "AIN1P") (class "Default")
      (node (ref "L1") (pin "P$2") (pinfunction "2_P$2") (pintype "passive"))
      (node (ref "OK1") (pin "4") (pinfunction "S1_4") (pintype "passive"))
      (node (ref "X1") (pin "1") (pinfunction "1_1") (pintype "passive"))
    )
    (net (code "15") (name "AIN2P") (class "Default")
      (node (ref "L2") (pin "P$2") (pinfunction "2_P$2") (pintype "passive"))
      (node (ref "OK3") (pin "4") (pinfunction "S1_4") (pintype "passive"))
      (node (ref "X1") (pin "3") (pinfunction "1_3") (pintype "passive"))
    )
    (net (code "16") (name "AIN3N") (class "Default")
      (node (ref "D11") (pin "2") (pinfunction "A_2") (pintype "passive"))
      (node (ref "D12") (pin "1") (pinfunction "C_1") (pintype "passive"))
      (node (ref "D7") (pin "2") (pinfunction "A_2") (pintype "passive"))
      (node (ref "D8") (pin "1") (pinfunction "C_1") (pintype "passive"))
      (node (ref "JP3") (pin "1") (pinfunction "1_1") (pintype "passive"))
      (node (ref "R32") (pin "2") (pinfunction "2_2") (pintype "passive"))
      (node (ref "R36") (pin "1") (pinfunction "1_1") (pintype "passive"))
      (node (ref "TVS1") (pin "C1") (pinfunction "1_C1") (pintype "passive"))
      (node (ref "X1") (pin "6") (pinfunction "1_6") (pintype "passive"))
    )
    (net (code "17") (name "AIN3P") (class "Default")
      (node (ref "F3") (pin "2") (pinfunction "2_2") (pintype "passive"))
      (node (ref "F4") (pin "2") (pinfunction "2_2") (pintype "passive"))
      (node (ref "X1") (pin "5") (pinfunction "1_5") (pintype "passive"))
    )
    (net (code "18") (name "AIN4N") (class "Default")
      (node (ref "D14") (pin "2") (pinfunction "A_2") (pintype "passive"))
      (node (ref "D15") (pin "1") (pinfunction "C_1") (pintype "passive"))
      (node (ref "D18") (pin "2") (pinfunction "A_2") (pintype "passive"))
      (node (ref "D19") (pin "1") (pinfunction "C_1") (pintype "passive"))
      (node (ref "JP4") (pin "1") (pinfunction "1_1") (pintype "passive"))
      (node (ref "R42") (pin "2") (pinfunction "2_2") (pintype "passive"))
      (node (ref "R46") (pin "1") (pinfunction "1_1") (pintype "passive"))
      (node (ref "TVS2") (pin "C1") (pinfunction "1_C1") (pintype "passive"))
      (node (ref "X1") (pin "8") (pinfunction "1_8") (pintype "passive"))
    )
    (net (code "19") (name "AIN4P") (class "Default")
      (node (ref "F5") (pin "2") (pinfunction "2_2") (pintype "passive"))
      (node (ref "ISEL10A_2") (pin "11") (pinfunction "COM_11") (pintype "passive"))
      (node (ref "ISEL10A_2") (pin "21") (pinfunction "COM_21") (pintype "passive"))
      (node (ref "X1") (pin "7") (pinfunction "1_7") (pintype "passive"))
    )
    (net (code "20") (name "AIN_U3") (class "Default")
      (node (ref "ISEL1A_1") (pin "10") (pinfunction "NC_10") (pintype "passive"))
      (node (ref "ISEL1A_1") (pin "3") (pinfunction "NC_3") (pintype "passive"))
      (node (ref "R37") (pin "2") (pinfunction "2_2") (pintype "passive"))
      (node (ref "R38") (pin "2") (pinfunction "2_2") (pintype "passive"))
      (node (ref "TVS1") (pin "C2") (pinfunction "2_C2") (pintype "passive"))
      (node (ref "X2") (pin "26") (pinfunction "1_26") (pintype "passive"))
    )
    (net (code "21") (name "AIN_U4") (class "Default")
      (node (ref "ISEL1A_2") (pin "10") (pinfunction "NC_10") (pintype "passive"))
      (node (ref "ISEL1A_2") (pin "3") (pinfunction "NC_3") (pintype "passive"))
      (node (ref "R47") (pin "2") (pinfunction "2_2") (pintype "passive"))
      (node (ref "R48") (pin "2") (pinfunction "2_2") (pintype "passive"))
      (node (ref "TVS2") (pin "C2") (pinfunction "2_C2") (pintype "passive"))
      (node (ref "X2") (pin "24") (pinfunction "1_24") (pintype "passive"))
    )
    (net (code "22") (name "AVSS") (class "Default")
      (node (ref "C11") (pin "1") (pinfunction "1_1") (pintype "passive"))
      (node (ref "C12") (pin "2") (pinfunction "2_2") (pintype "passive"))
      (node (ref "C13") (pin "1") (pinfunction "1_1") (pintype "passive"))
      (node (ref "C14") (pin "2") (pinfunction "2_2") (pintype "passive"))
      (node (ref "C15") (pin "1") (pinfunction "1_1") (pintype "passive"))
      (node (ref "C16") (pin "2") (pinfunction "2_2") (pintype "passive"))
      (node (ref "C17") (pin "1") (pinfunction "1_1") (pintype "passive"))
      (node (ref "C18") (pin "2") (pinfunction "2_2") (pintype "passive"))
      (node (ref "C19") (pin "-") (pinfunction "-_-") (pintype "passive"))
      (node (ref "C20") (pin "2") (pinfunction "2_2") (pintype "passive"))
      (node (ref "C25") (pin "1") (pinfunction "1_1") (pintype "passive"))
      (node (ref "C26") (pin "2") (pinfunction "2_2") (pintype "passive"))
      (node (ref "C29") (pin "2") (pinfunction "2_2") (pintype "passive"))
      (node (ref "C30") (pin "1") (pinfunction "1_1") (pintype "passive"))
      (node (ref "C34") (pin "1") (pinfunction "1_1") (pintype "passive"))
      (node (ref "C35") (pin "1") (pinfunction "1_1") (pintype "passive"))
      (node (ref "IC10") (pin "3") (pinfunction "GND_3") (pintype "power_in"))
      (node (ref "IC10") (pin "4") (pinfunction "GND_4") (pintype "power_in"))
      (node (ref "IC10") (pin "5") (pinfunction "GND_5") (pintype "power_in"))
      (node (ref "IC10") (pin "8") (pinfunction "GND_8") (pintype "power_in"))
      (node (ref "IC11") (pin "20") (pinfunction "AVSS_2_20") (pintype "power_in"))
      (node (ref "IC11") (pin "23") (pinfunction "AVSS_3_23") (pintype "power_in"))
      (node (ref "IC11") (pin "25") (pinfunction "VREFN_25") (pintype "input"))
      (node (ref "IC11") (pin "32") (pinfunction "AVSS_4_32") (pintype "power_in"))
      (node (ref "IC11") (pin "53") (pinfunction "AVSS1_53") (pintype "power_in"))
      (node (ref "IC11") (pin "57") (pinfunction "AVSS_5_57") (pintype "power_in"))
      (node (ref "IC11") (pin "58") (pinfunction "AVSS_58") (pintype "power_in"))
      (node (ref "R54") (pin "1") (pinfunction "1_1") (pintype "passive"))
    )
    (net (code "23") (name "GND") (class "Default")
      (node (ref "C1") (pin "1") (pinfunction "1_1") (pintype "passive"))
      (node (ref "C10") (pin "1") (pinfunction "1_1") (pintype "passive"))
      (node (ref "C2") (pin "1") (pinfunction "1_1") (pintype "passive"))
      (node (ref "C21") (pin "2") (pinfunction "2_2") (pintype "passive"))
      (node (ref "C22") (pin "2") (pinfunction "2_2") (pintype "passive"))
      (node (ref "C23") (pin "1") (pinfunction "1_1") (pintype "passive"))
      (node (ref "C24") (pin "1") (pinfunction "1_1") (pintype "passive"))
      (node (ref "C27") (pin "2") (pinfunction "2_2") (pintype "passive"))
      (node (ref "C28") (pin "2") (pinfunction "2_2") (pintype "passive"))
      (node (ref "C3") (pin "2") (pinfunction "2_2") (pintype "passive"))
      (node (ref "C31") (pin "2") (pinfunction "2_2") (pintype "passive"))
      (node (ref "C32") (pin "1") (pinfunction "1_1") (pintype "passive"))
      (node (ref "C33") (pin "1") (pinfunction "1_1") (pintype "passive"))
      (node (ref "C34") (pin "2") (pinfunction "2_2") (pintype "passive"))
      (node (ref "C35") (pin "2") (pinfunction "2_2") (pintype "passive"))
      (node (ref "C4") (pin "1") (pinfunction "1_1") (pintype "passive"))
      (node (ref "C5") (pin "1") (pinfunction "1_1") (pintype "passive"))
      (node (ref "C6") (pin "1") (pinfunction "1_1") (pintype "passive"))
      (node (ref "C7") (pin "1") (pinfunction "1_1") (pintype "passive"))
      (node (ref "C8") (pin "2") (pinfunction "2_2") (pintype "passive"))
      (node (ref "C9") (pin "1") (pinfunction "1_1") (pintype "passive"))
      (node (ref "D14") (pin "1") (pinfunction "C_1") (pintype "passive"))
      (node (ref "D15") (pin "2") (pinfunction "A_2") (pintype "passive"))
      (node (ref "D2") (pin "1") (pinfunction "C_1") (pintype "passive"))
      (node (ref "D3") (pin "2") (pinfunction "A_2") (pintype "passive"))
      (node (ref "D5") (pin "1") (pinfunction "C_1") (pintype "passive"))
      (node (ref "D6") (pin "2") (pinfunction "A_2") (pintype "passive"))
      (node (ref "D7") (pin "1") (pinfunction "C_1") (pintype "passive"))
      (node (ref "D8") (pin "2") (pinfunction "A_2") (pintype "passive"))
      (node (ref "GND") (pin "1") (pinfunction "P$1_1") (pintype "bidirectional"))
      (node (ref "IC11") (pin "31") (pinfunction "RESV1_31") (pintype "input"))
      (node (ref "IC11") (pin "33") (pinfunction "DGND_2_33") (pintype "power_in"))
      (node (ref "IC11") (pin "41") (pinfunction "DAISY_IN_41") (pintype "input"))
      (node (ref "IC11") (pin "49") (pinfunction "DGND_3_49") (pintype "power_in"))
      (node (ref "IC11") (pin "51") (pinfunction "DGND_51") (pintype "power_in"))
      (node (ref "IC12") (pin "2") (pinfunction "GND_2") (pintype "passive"))
      (node (ref "IC13") (pin "1") (pinfunction "GND_1") (pintype "passive"))
      (node (ref "IC2") (pin "5") (pinfunction "GND_5") (pintype "power_in"))
      (node (ref "IC3") (pin "9") (pinfunction "GND_9") (pintype "input"))
      (node (ref "IC5") (pin "5") (pinfunction "GND_5") (pintype "power_in"))
      (node (ref "IC7") (pin "5") (pinfunction "GND_5") (pintype "power_in"))
      (node (ref "IC9") (pin "5") (pinfunction "GND_5") (pintype "power_in"))
      (node (ref "JP1") (pin "2") (pinfunction "2_2") (pintype "passive"))
      (node (ref "JP2") (pin "2") (pinfunction "2_2") (pintype "passive"))
      (node (ref "JP3") (pin "2") (pinfunction "2_2") (pintype "passive"))
      (node (ref "JP4") (pin "2") (pinfunction "2_2") (pintype "passive"))
      (node (ref "JP5") (pin "NO") (pinfunction "NO_NO") (pintype "passive"))
      (node (ref "OK1") (pin "2") (pinfunction "C_2") (pintype "passive"))
      (node (ref "OK2") (pin "2") (pinfunction "C_2") (pintype "passive"))
      (node (ref "OK3") (pin "2") (pinfunction "C_2") (pintype "passive"))
      (node (ref "OK4") (pin "2") (pinfunction "C_2") (pintype "passive"))
      (node (ref "R11") (pin "1") (pinfunction "1_1") (pintype "passive"))
      (node (ref "R24") (pin "1") (pinfunction "1_1") (pintype "passive"))
      (node (ref "R32") (pin "1") (pinfunction "1_1") (pintype "passive"))
      (node (ref "R42") (pin "1") (pinfunction "1_1") (pintype "passive"))
      (node (ref "R5") (pin "2") (pinfunction "2_2") (pintype "passive"))
      (node (ref "R7") (pin "1") (pinfunction "1_1") (pintype "passive"))
      (node (ref "S1") (pin "SH.1") (pinfunction "SH_SH.1") (pintype "passive"))
      (node (ref "S1") (pin "SH.2") (pinfunction "SH_SH.2") (pintype "passive"))
      (node (ref "S1") (pin "SH.3") (pinfunction "SH_SH.3") (pintype "passive"))
      (node (ref "S1") (pin "SH.4") (pinfunction "SH_SH.4") (pintype "passive"))
      (node (ref "S1") (pin "SH.5") (pinfunction "SH_SH.5") (pintype "passive"))
      (node (ref "S1") (pin "SH.6") (pinfunction "SH_SH.6") (pintype "passive"))
      (node (ref "S1") (pin "SH.7") (pinfunction "SH_SH.7") (pintype "passive"))
      (node (ref "S1") (pin "SH.8") (pinfunction "SH_SH.8") (pintype "passive"))
      (node (ref "X2") (pin "1") (pinfunction "1_1") (pintype "passive"))
      (node (ref "X2") (pin "11") (pinfunction "1_11") (pintype "passive"))
      (node (ref "X2") (pin "12") (pinfunction "1_12") (pintype "passive"))
      (node (ref "X2") (pin "2") (pinfunction "1_2") (pintype "passive"))
      (node (ref "X2") (pin "21") (pinfunction "1_21") (pintype "passive"))
      (node (ref "X2") (pin "22") (pinfunction "1_22") (pintype "passive"))
      (node (ref "X2") (pin "27") (pinfunction "1_27") (pintype "passive"))
      (node (ref "X2") (pin "28") (pinfunction "1_28") (pintype "passive"))
      (node (ref "X3") (pin "1") (pinfunction "1_1") (pintype "passive"))
      (node (ref "X3") (pin "2") (pinfunction "1_2") (pintype "passive"))
      (node (ref "X3") (pin "27") (pinfunction "1_27") (pintype "passive"))
      (node (ref "X3") (pin "28") (pinfunction "1_28") (pintype "passive"))
      (node (ref "XO1") (pin "3") (pinfunction "GND_3") (pintype "power_in"))
    )
    (net (code "24") (name "HI_CLAMP") (class "Default")
      (node (ref "IC1") (pin "12") (pinfunction "+IN_12") (pintype "input"))
      (node (ref "IC1") (pin "3") (pinfunction "+IN_3") (pintype "input"))
      (node (ref "IC4") (pin "12") (pinfunction "+IN_12") (pintype "input"))
      (node (ref "IC4") (pin "3") (pinfunction "+IN_3") (pintype "input"))
      (node (ref "R2") (pin "2") (pinfunction "2_2") (pintype "passive"))
      (node (ref "R5") (pin "1") (pinfunction "1_1") (pintype "passive"))
    )
    (net (code "25") (name "IN1N") (class "Default")
      (node (ref "D2") (pin "2") (pinfunction "A_2") (pintype "passive"))
      (node (ref "D3") (pin "1") (pinfunction "C_1") (pintype "passive"))
      (node (ref "IC11") (pin "15") (pinfunction "IN1N_15") (pintype "input"))
      (node (ref "JP1") (pin "1") (pinfunction "1_1") (pintype "passive"))
      (node (ref "R11") (pin "2") (pinfunction "2_2") (pintype "passive"))
      (node (ref "R17") (pin "1") (pinfunction "1_1") (pintype "passive"))
      (node (ref "R4") (pin "1") (pinfunction "1_1") (pintype "passive"))
      (node (ref "X1") (pin "2") (pinfunction "1_2") (pintype "passive"))
    )
    (net (code "26") (name "IN1P") (class "Default")
      (node (ref "D1") (pin "3") (pinfunction "AC_3") (pintype "passive"))
      (node (ref "IC1") (pin "13") (pinfunction "-IN_13") (pintype "input"))
      (node (ref "IC1") (pin "9") (pinfunction "-IN_9") (pintype "input"))
      (node (ref "IC11") (pin "16") (pinfunction "IN1P_16") (pintype "input"))
      (node (ref "IC2") (pin "10") (pinfunction "D_10") (pintype "bidirectional"))
      (node (ref "IC2") (pin "15") (pinfunction "D_15") (pintype "bidirectional"))
      (node (ref "IC2") (pin "2") (pinfunction "D_2") (pintype "bidirectional"))
      (node (ref "IC2") (pin "7") (pinfunction "D_7") (pintype "bidirectional"))
    )
    (net (code "27") (name "IN2N") (class "Default")
      (node (ref "D5") (pin "2") (pinfunction "A_2") (pintype "passive"))
      (node (ref "D6") (pin "1") (pinfunction "C_1") (pintype "passive"))
      (node (ref "IC11") (pin "13") (pinfunction "IN2N_13") (pintype "input"))
      (node (ref "JP2") (pin "1") (pinfunction "1_1") (pintype "passive"))
      (node (ref "R20") (pin "1") (pinfunction "1_1") (pintype "passive"))
      (node (ref "R24") (pin "2") (pinfunction "2_2") (pintype "passive"))
      (node (ref "R30") (pin "1") (pinfunction "1_1") (pintype "passive"))
      (node (ref "X1") (pin "4") (pinfunction "1_4") (pintype "passive"))
    )
    (net (code "28") (name "IN2P") (class "Default")
      (node (ref "D4") (pin "3") (pinfunction "AC_3") (pintype "passive"))
      (node (ref "IC11") (pin "14") (pinfunction "IN2P_14") (pintype "input"))
      (node (ref "IC4") (pin "13") (pinfunction "-IN_13") (pintype "input"))
      (node (ref "IC4") (pin "9") (pinfunction "-IN_9") (pintype "input"))
      (node (ref "IC5") (pin "10") (pinfunction "D_10") (pintype "bidirectional"))
      (node (ref "IC5") (pin "15") (pinfunction "D_15") (pintype "bidirectional"))
      (node (ref "IC5") (pin "2") (pinfunction "D_2") (pintype "bidirectional"))
      (node (ref "IC5") (pin "7") (pinfunction "D_7") (pintype "bidirectional"))
    )
    (net (code "29") (name "IN3N") (class "Default")
      (node (ref "IC11") (pin "11") (pinfunction "IN3N_11") (pintype "input"))
      (node (ref "R36") (pin "1S") (pinfunction "1S_1S") (pintype "passive"))
      (node (ref "R40") (pin "1") (pinfunction "1_1") (pintype "passive"))
      (node (ref "X2") (pin "25") (pinfunction "1_25") (pintype "passive"))
    )
    (net (code "30") (name "IN3P") (class "Default")
      (node (ref "D13") (pin "3") (pinfunction "AC_3") (pintype "passive"))
      (node (ref "IC11") (pin "12") (pinfunction "IN3P_12") (pintype "input"))
      (node (ref "IC4") (pin "2") (pinfunction "-IN_2") (pintype "input"))
      (node (ref "IC4") (pin "6") (pinfunction "-IN_6") (pintype "input"))
      (node (ref "IC7") (pin "11") (pinfunction "S_11") (pintype "bidirectional"))
      (node (ref "IC7") (pin "15") (pinfunction "D_15") (pintype "bidirectional"))
      (node (ref "IC7") (pin "3") (pinfunction "S_3") (pintype "bidirectional"))
      (node (ref "IC7") (pin "7") (pinfunction "D_7") (pintype "bidirectional"))
    )
    (net (code "31") (name "IN4N") (class "Default")
      (node (ref "IC11") (pin "9") (pinfunction "IN4N_9") (pintype "input"))
      (node (ref "R46") (pin "1S") (pinfunction "1S_1S") (pintype "passive"))
      (node (ref "R50") (pin "1") (pinfunction "1_1") (pintype "passive"))
      (node (ref "X2") (pin "23") (pinfunction "1_23") (pintype "passive"))
    )
    (net (code "32") (name "IN4P") (class "Default")
      (node (ref "D20") (pin "3") (pinfunction "AC_3") (pintype "passive"))
      (node (ref "IC1") (pin "2") (pinfunction "-IN_2") (pintype "input"))
      (node (ref "IC1") (pin "6") (pinfunction "-IN_6") (pintype "input"))
      (node (ref "IC11") (pin "10") (pinfunction "IN4P_10") (pintype "input"))
      (node (ref "IC9") (pin "10") (pinfunction "D_10") (pintype "bidirectional"))
      (node (ref "IC9") (pin "14") (pinfunction "S_14") (pintype "bidirectional"))
      (node (ref "IC9") (pin "3") (pinfunction "S_3") (pintype "bidirectional"))
      (node (ref "IC9") (pin "7") (pinfunction "D_7") (pintype "bidirectional"))
    )
    (net (code "33") (name "ISEL#1") (class "Default")
      (node (ref "IC2") (pin "9") (pinfunction "IN_9") (pintype "input"))
      (node (ref "R3") (pin "2") (pinfunction "2_2") (pintype "passive"))
      (node (ref "X3") (pin "3") (pinfunction "1_3") (pintype "passive"))
    )
    (net (code "34") (name "ISEL#2") (class "Default")
      (node (ref "IC5") (pin "9") (pinfunction "IN_9") (pintype "input"))
      (node (ref "R19") (pin "2") (pinfunction "2_2") (pintype "passive"))
      (node (ref "X3") (pin "4") (pinfunction "1_4") (pintype "passive"))
    )
    (net (code "35") (name "ISEL10A_R3_OUT") (class "Default")
      (node (ref "IC3") (pin "15") (pinfunction "4C_15") (pintype "output"))
      (node (ref "ISEL10A_1") (pin "A1") (pinfunction "R_A1") (pintype "passive"))
    )
    (net (code "36") (name "ISEL10A_R4_OUT") (class "Default")
      (node (ref "IC3") (pin "11") (pinfunction "8C_11") (pintype "output"))
      (node (ref "ISEL10A_2") (pin "A1") (pinfunction "R_A1") (pintype "passive"))
    )
    (net (code "37") (name "ISEL10A_S3_OUT") (class "Default")
      (node (ref "IC3") (pin "16") (pinfunction "3C_16") (pintype "output"))
      (node (ref "ISEL10A_1") (pin "A2") (pinfunction "S_A2") (pintype "passive"))
    )
    (net (code "38") (name "ISEL10A_S4_OUT") (class "Default")
      (node (ref "IC3") (pin "12") (pinfunction "7C_12") (pintype "output"))
      (node (ref "ISEL10A_2") (pin "A2") (pinfunction "S_A2") (pintype "passive"))
    )
    (net (code "39") (name "ISEL10_R#3") (class "Default")
      (node (ref "IC3") (pin "4") (pinfunction "4B_4") (pintype "input"))
      (node (ref "X3") (pin "21") (pinfunction "1_21") (pintype "passive"))
    )
    (net (code "40") (name "ISEL10_R#4") (class "Default")
      (node (ref "IC3") (pin "8") (pinfunction "8B_8") (pintype "input"))
      (node (ref "X3") (pin "22") (pinfunction "1_22") (pintype "passive"))
    )
    (net (code "41") (name "ISEL10_S#3") (class "Default")
      (node (ref "IC3") (pin "3") (pinfunction "3B_3") (pintype "input"))
      (node (ref "X3") (pin "19") (pinfunction "1_19") (pintype "passive"))
    )
    (net (code "42") (name "ISEL10_S#4") (class "Default")
      (node (ref "IC3") (pin "7") (pinfunction "7B_7") (pintype "input"))
      (node (ref "X3") (pin "20") (pinfunction "1_20") (pintype "passive"))
    )
    (net (code "43") (name "ISEL_LOW#3") (class "Default")
      (node (ref "IC7") (pin "16") (pinfunction "IN_16") (pintype "input"))
      (node (ref "X3") (pin "23") (pinfunction "1_23") (pintype "passive"))
    )
    (net (code "44") (name "ISEL_LOW#4") (class "Default")
      (node (ref "IC9") (pin "9") (pinfunction "IN_9") (pintype "input"))
      (node (ref "X3") (pin "24") (pinfunction "1_24") (pintype "passive"))
    )
    (net (code "45") (name "ISEL_MID#3") (class "Default")
      (node (ref "IC7") (pin "9") (pinfunction "IN_9") (pintype "input"))
      (node (ref "Q5") (pin "1") (pinfunction "G_1") (pintype "passive"))
      (node (ref "Q6") (pin "1") (pinfunction "G_1") (pintype "passive"))
      (node (ref "X3") (pin "25") (pinfunction "1_25") (pintype "passive"))
    )
    (net (code "46") (name "ISEL_MID#4") (class "Default")
      (node (ref "IC9") (pin "16") (pinfunction "IN_16") (pintype "input"))
      (node (ref "Q7") (pin "1") (pinfunction "G_1") (pintype "passive"))
      (node (ref "Q8") (pin "1") (pinfunction "G_1") (pintype "passive"))
      (node (ref "X3") (pin "26") (pinfunction "1_26") (pintype "passive"))
    )
    (net (code "47") (name "ISEL_R#3") (class "Default")
      (node (ref "IC3") (pin "2") (pinfunction "2B_2") (pintype "input"))
      (node (ref "X3") (pin "17") (pinfunction "1_17") (pintype "passive"))
    )
    (net (code "48") (name "ISEL_R#4") (class "Default")
      (node (ref "IC3") (pin "6") (pinfunction "6B_6") (pintype "input"))
      (node (ref "X3") (pin "18") (pinfunction "1_18") (pintype "passive"))
    )
    (net (code "49") (name "ISEL_R3_OUT") (class "Default")
      (node (ref "IC3") (pin "17") (pinfunction "2C_17") (pintype "output"))
      (node (ref "ISEL1A_1") (pin "7") (pinfunction "R-_7") (pintype "passive"))
    )
    (net (code "50") (name "ISEL_R4_OUT") (class "Default")
      (node (ref "IC3") (pin "13") (pinfunction "6C_13") (pintype "output"))
      (node (ref "ISEL1A_2") (pin "7") (pinfunction "R-_7") (pintype "passive"))
    )
    (net (code "51") (name "ISEL_S#3") (class "Default")
      (node (ref "IC3") (pin "1") (pinfunction "1B_1") (pintype "input"))
      (node (ref "X3") (pin "15") (pinfunction "1_15") (pintype "passive"))
    )
    (net (code "52") (name "ISEL_S#4") (class "Default")
      (node (ref "IC3") (pin "5") (pinfunction "5B_5") (pintype "input"))
      (node (ref "X3") (pin "16") (pinfunction "1_16") (pintype "passive"))
    )
    (net (code "53") (name "ISEL_S3_OUT") (class "Default")
      (node (ref "IC3") (pin "18") (pinfunction "1C_18") (pintype "output"))
      (node (ref "ISEL1A_1") (pin "12") (pinfunction "S-_12") (pintype "passive"))
    )
    (net (code "54") (name "ISEL_S4_OUT") (class "Default")
      (node (ref "IC3") (pin "14") (pinfunction "5C_14") (pintype "output"))
      (node (ref "ISEL1A_2") (pin "12") (pinfunction "S-_12") (pintype "passive"))
    )
    (net (code "55") (name "LO_CLAMP") (class "Default")
      (node (ref "IC1") (pin "10") (pinfunction "+IN_10") (pintype "input"))
      (node (ref "IC1") (pin "5") (pinfunction "+IN_5") (pintype "input"))
      (node (ref "IC4") (pin "10") (pinfunction "+IN_10") (pintype "input"))
      (node (ref "IC4") (pin "5") (pinfunction "+IN_5") (pintype "input"))
      (node (ref "R10") (pin "1") (pinfunction "1_1") (pintype "passive"))
      (node (ref "R7") (pin "2") (pinfunction "2_2") (pintype "passive"))
    )
    (net (code "56") (name "Net-(D1-A)") (class "Default")
      (node (ref "D1") (pin "1") (pinfunction "A_1") (pintype "passive"))
      (node (ref "IC1") (pin "8") (pinfunction "OUT_8") (pintype "output"))
    )
    (net (code "57") (name "Net-(D1-C)") (class "Default")
      (node (ref "D1") (pin "2") (pinfunction "C_2") (pintype "passive"))
      (node (ref "IC1") (pin "14") (pinfunction "OUT_14") (pintype "output"))
    )
    (net (code "58") (name "Net-(D4-A)") (class "Default")
      (node (ref "D4") (pin "1") (pinfunction "A_1") (pintype "passive"))
      (node (ref "IC4") (pin "8") (pinfunction "OUT_8") (pintype "output"))
    )
    (net (code "59") (name "Net-(D4-C)") (class "Default")
      (node (ref "D4") (pin "2") (pinfunction "C_2") (pintype "passive"))
      (node (ref "IC4") (pin "14") (pinfunction "OUT_14") (pintype "output"))
    )
    (net (code "60") (name "Net-(D10-A)") (class "Default")
      (node (ref "D10") (pin "2") (pinfunction "A_2") (pintype "passive"))
      (node (ref "D11") (pin "1") (pinfunction "C_1") (pintype "passive"))
      (node (ref "D12") (pin "2") (pinfunction "A_2") (pintype "passive"))
      (node (ref "D9") (pin "1") (pinfunction "C_1") (pintype "passive"))
      (node (ref "R35") (pin "2") (pinfunction "2_2") (pintype "passive"))
    )
    (net (code "61") (name "Net-(D10-C)") (class "Default")
      (node (ref "D10") (pin "1") (pinfunction "C_1") (pintype "passive"))
      (node (ref "D9") (pin "2") (pinfunction "A_2") (pintype "passive"))
      (node (ref "IC7") (pin "14") (pinfunction "S_14") (pintype "bidirectional"))
      (node (ref "ISEL1A_1") (pin "5") (pinfunction "NO_5") (pintype "passive"))
      (node (ref "ISEL1A_1") (pin "8") (pinfunction "NO_8") (pintype "passive"))
      (node (ref "Q5") (pin "2") (pinfunction "S_2") (pintype "passive"))
      (node (ref "R31") (pin "2") (pinfunction "2_2") (pintype "passive"))
      (node (ref "R34") (pin "2") (pinfunction "2_2") (pintype "passive"))
    )
    (net (code "62") (name "Net-(D13-A)") (class "Default")
      (node (ref "D13") (pin "1") (pinfunction "A_1") (pintype "passive"))
      (node (ref "IC4") (pin "7") (pinfunction "OUT_7") (pintype "output"))
    )
    (net (code "63") (name "Net-(D13-C)") (class "Default")
      (node (ref "D13") (pin "2") (pinfunction "C_2") (pintype "passive"))
      (node (ref "IC4") (pin "1") (pinfunction "OUT_1") (pintype "output"))
    )
    (net (code "64") (name "Net-(D16-A)") (class "Default")
      (node (ref "D16") (pin "2") (pinfunction "A_2") (pintype "passive"))
      (node (ref "D17") (pin "1") (pinfunction "C_1") (pintype "passive"))
      (node (ref "IC9") (pin "11") (pinfunction "S_11") (pintype "bidirectional"))
      (node (ref "ISEL1A_2") (pin "5") (pinfunction "NO_5") (pintype "passive"))
      (node (ref "ISEL1A_2") (pin "8") (pinfunction "NO_8") (pintype "passive"))
      (node (ref "Q7") (pin "2") (pinfunction "S_2") (pintype "passive"))
      (node (ref "R41") (pin "2") (pinfunction "2_2") (pintype "passive"))
      (node (ref "R44") (pin "2") (pinfunction "2_2") (pintype "passive"))
    )
    (net (code "65") (name "Net-(D16-C)") (class "Default")
      (node (ref "D16") (pin "1") (pinfunction "C_1") (pintype "passive"))
      (node (ref "D17") (pin "2") (pinfunction "A_2") (pintype "passive"))
      (node (ref "D18") (pin "1") (pinfunction "C_1") (pintype "passive"))
      (node (ref "D19") (pin "2") (pinfunction "A_2") (pintype "passive"))
      (node (ref "R45") (pin "2") (pinfunction "2_2") (pintype "passive"))
    )
    (net (code "66") (name "Net-(D20-A)") (class "Default")
      (node (ref "D20") (pin "1") (pinfunction "A_1") (pintype "passive"))
      (node (ref "IC1") (pin "7") (pinfunction "OUT_7") (pintype "output"))
    )
    (net (code "67") (name "Net-(D20-C)") (class "Default")
      (node (ref "D20") (pin "2") (pinfunction "C_2") (pintype "passive"))
      (node (ref "IC1") (pin "1") (pinfunction "OUT_1") (pintype "output"))
    )
    (net (code "68") (name "Net-(F1-P$1)") (class "Default")
      (node (ref "F1") (pin "1") (pinfunction "P$1_1") (pintype "bidirectional"))
      (node (ref "R1") (pin "1") (pinfunction "1_1") (pintype "passive"))
    )
    (net (code "69") (name "Net-(F1-P$2)") (class "Default")
      (node (ref "F1") (pin "2") (pinfunction "P$2_2") (pintype "bidirectional"))
      (node (ref "Q1") (pin "1") (pinfunction "G_1") (pintype "passive"))
      (node (ref "Q2") (pin "3") (pinfunction "S_3") (pintype "passive"))
    )
    (net (code "70") (name "Net-(F2-P$1)") (class "Default")
      (node (ref "F2") (pin "1") (pinfunction "P$1_1") (pintype "bidirectional"))
      (node (ref "R18") (pin "1") (pinfunction "1_1") (pintype "passive"))
    )
    (net (code "71") (name "Net-(F2-P$2)") (class "Default")
      (node (ref "F2") (pin "2") (pinfunction "P$2_2") (pintype "bidirectional"))
      (node (ref "Q3") (pin "1") (pinfunction "G_1") (pintype "passive"))
      (node (ref "Q4") (pin "3") (pinfunction "S_3") (pintype "passive"))
    )
    (net (code "72") (name "Net-(F6-Pad2)") (class "Default")
      (node (ref "F6") (pin "2") (pinfunction "2_2") (pintype "passive"))
      (node (ref "R46") (pin "2") (pinfunction "2_2") (pintype "passive"))
    )
    (net (code "73") (name "Net-(IC2A-S)") (class "Default")
      (node (ref "IC2") (pin "3") (pinfunction "S_3") (pintype "bidirectional"))
      (node (ref "R14") (pin "1") (pinfunction "1_1") (pintype "passive"))
      (node (ref "R15") (pin "2") (pinfunction "2_2") (pintype "passive"))
    )
    (net (code "74") (name "Net-(IC2B-S)") (class "Default")
      (node (ref "IC2") (pin "14") (pinfunction "S_14") (pintype "bidirectional"))
      (node (ref "R16") (pin "1") (pinfunction "1_1") (pintype "passive"))
      (node (ref "R17") (pin "2") (pinfunction "2_2") (pintype "passive"))
    )
    (net (code "75") (name "Net-(IC2C-S)") (class "Default")
      (node (ref "IC2") (pin "11") (pinfunction "S_11") (pintype "bidirectional"))
      (node (ref "Q2") (pin "2") (pinfunction "D_2") (pintype "passive"))
      (node (ref "Q2") (pin "4") (pinfunction "D_4") (pintype "passive"))
      (node (ref "R4") (pin "2") (pinfunction "2_2") (pintype "passive"))
    )
    (net (code "76") (name "Net-(IC2D-S)") (class "Default")
      (node (ref "IC2") (pin "6") (pinfunction "S_6") (pintype "bidirectional"))
      (node (ref "OK2") (pin "4") (pinfunction "S1_4") (pintype "passive"))
    )
    (net (code "77") (name "Net-(IC3-COM)") (class "Default")
      (node (ref "IC3") (pin "10") (pinfunction "COM_10") (pintype "passive"))
      (node (ref "ZD1") (pin "C") (pinfunction "C_C") (pintype "passive"))
    )
    (net (code "78") (name "Net-(IC5A-S)") (class "Default")
      (node (ref "IC5") (pin "3") (pinfunction "S_3") (pintype "bidirectional"))
      (node (ref "R27") (pin "1") (pinfunction "1_1") (pintype "passive"))
      (node (ref "R28") (pin "2") (pinfunction "2_2") (pintype "passive"))
    )
    (net (code "79") (name "Net-(IC5B-S)") (class "Default")
      (node (ref "IC5") (pin "14") (pinfunction "S_14") (pintype "bidirectional"))
      (node (ref "R29") (pin "1") (pinfunction "1_1") (pintype "passive"))
      (node (ref "R30") (pin "2") (pinfunction "2_2") (pintype "passive"))
    )
    (net (code "80") (name "Net-(IC5C-S)") (class "Default")
      (node (ref "IC5") (pin "11") (pinfunction "S_11") (pintype "bidirectional"))
      (node (ref "Q4") (pin "2") (pinfunction "D_2") (pintype "passive"))
      (node (ref "Q4") (pin "4") (pinfunction "D_4") (pintype "passive"))
      (node (ref "R20") (pin "2") (pinfunction "2_2") (pintype "passive"))
    )
    (net (code "81") (name "Net-(IC5D-S)") (class "Default")
      (node (ref "IC5") (pin "6") (pinfunction "S_6") (pintype "bidirectional"))
      (node (ref "OK4") (pin "4") (pinfunction "S1_4") (pintype "passive"))
    )
    (net (code "82") (name "Net-(IC6A-+IN)") (class "Default")
      (node (ref "IC6") (pin "3") (pinfunction "+IN_3") (pintype "input"))
      (node (ref "R34") (pin "1") (pinfunction "1_1") (pintype "passive"))
    )
    (net (code "83") (name "Net-(IC6A--IN)") (class "Default")
      (node (ref "IC6") (pin "1") (pinfunction "OUT_1") (pintype "output"))
      (node (ref "IC6") (pin "4") (pinfunction "-IN_4") (pintype "input"))
      (node (ref "R35") (pin "1") (pinfunction "1_1") (pintype "passive"))
    )
    (net (code "84") (name "Net-(IC7A-D)") (class "Default")
      (node (ref "IC7") (pin "2") (pinfunction "D_2") (pintype "bidirectional"))
      (node (ref "R39") (pin "1") (pinfunction "1_1") (pintype "passive"))
      (node (ref "R40") (pin "2") (pinfunction "2_2") (pintype "passive"))
    )
    (net (code "85") (name "Net-(IC7C-D)") (class "Default")
      (node (ref "IC7") (pin "10") (pinfunction "D_10") (pintype "bidirectional"))
      (node (ref "R33") (pin "2S") (pinfunction "2S_2S") (pintype "passive"))
    )
    (net (code "86") (name "Net-(IC7D-S)") (class "Default")
      (node (ref "IC7") (pin "6") (pinfunction "S_6") (pintype "bidirectional"))
      (node (ref "R37") (pin "1") (pinfunction "1_1") (pintype "passive"))
    )
    (net (code "87") (name "Net-(IC8A-+IN)") (class "Default")
      (node (ref "IC8") (pin "3") (pinfunction "+IN_3") (pintype "input"))
      (node (ref "R44") (pin "1") (pinfunction "1_1") (pintype "passive"))
    )
    (net (code "88") (name "Net-(IC8A--IN)") (class "Default")
      (node (ref "IC8") (pin "1") (pinfunction "OUT_1") (pintype "output"))
      (node (ref "IC8") (pin "4") (pinfunction "-IN_4") (pintype "input"))
      (node (ref "R45") (pin "1") (pinfunction "1_1") (pintype "passive"))
    )
    (net (code "89") (name "Net-(IC9A-D)") (class "Default")
      (node (ref "IC9") (pin "2") (pinfunction "D_2") (pintype "bidirectional"))
      (node (ref "R49") (pin "1") (pinfunction "1_1") (pintype "passive"))
      (node (ref "R50") (pin "2") (pinfunction "2_2") (pintype "passive"))
    )
    (net (code "90") (name "Net-(IC9B-D)") (class "Default")
      (node (ref "IC9") (pin "15") (pinfunction "D_15") (pintype "bidirectional"))
      (node (ref "R43") (pin "2S") (pinfunction "2S_2S") (pintype "passive"))
    )
    (net (code "91") (name "Net-(IC9D-S)") (class "Default")
      (node (ref "IC9") (pin "6") (pinfunction "S_6") (pintype "bidirectional"))
      (node (ref "R47") (pin "1") (pinfunction "1_1") (pintype "passive"))
    )
    (net (code "92") (name "Net-(IC10-VOUT_F)") (class "Default")
      (node (ref "C16") (pin "1") (pinfunction "1_1") (pintype "passive"))
      (node (ref "C18") (pin "1") (pinfunction "1_1") (pintype "passive"))
      (node (ref "C19") (pin "+") (pinfunction "+_+") (pintype "passive"))
      (node (ref "C20") (pin "1") (pinfunction "1_1") (pintype "passive"))
      (node (ref "IC10") (pin "6") (pinfunction "VOUT_S_6") (pintype "output"))
      (node (ref "IC10") (pin "7") (pinfunction "VOUT_F_7") (pintype "output"))
      (node (ref "IC11") (pin "24") (pinfunction "VREFP_24") (pintype "bidirectional"))
    )
    (net (code "93") (name "Net-(IC11-AVDD)") (class "Default")
      (node (ref "C25") (pin "2") (pinfunction "2_2") (pintype "passive"))
      (node (ref "C26") (pin "1") (pinfunction "1_1") (pintype "passive"))
      (node (ref "C27") (pin "1") (pinfunction "1_1") (pintype "passive"))
      (node (ref "C28") (pin "1") (pinfunction "1_1") (pintype "passive"))
      (node (ref "C29") (pin "1") (pinfunction "1_1") (pintype "passive"))
      (node (ref "C30") (pin "2") (pinfunction "2_2") (pintype "passive"))
      (node (ref "IC11") (pin "19") (pinfunction "AVDD_2_19") (pintype "power_in"))
      (node (ref "IC11") (pin "21") (pinfunction "AVDD_3_21") (pintype "power_in"))
      (node (ref "IC11") (pin "22") (pinfunction "AVDD_4_22") (pintype "power_in"))
      (node (ref "IC11") (pin "54") (pinfunction "AVDD1_54") (pintype "power_in"))
      (node (ref "IC11") (pin "56") (pinfunction "AVDD_5_56") (pintype "power_in"))
      (node (ref "IC11") (pin "59") (pinfunction "AVDD_59") (pintype "power_in"))
      (node (ref "R53") (pin "2") (pinfunction "2_2") (pintype "passive"))
    )
    (net (code "94") (name "Net-(IC11-CLK)") (class "Default")
      (node (ref "IC11") (pin "37") (pinfunction "CLK_37") (pintype "input"))
      (node (ref "JP6") (pin "COM") (pinfunction "COM_COM") (pintype "passive"))
    )
    (net (code "95") (name "Net-(IC11-CLKSEL)") (class "Default")
      (node (ref "IC11") (pin "52") (pinfunction "CLKSEL_52") (pintype "input"))
      (node (ref "R52") (pin "1") (pinfunction "1_1") (pintype "passive"))
    )
    (net (code "96") (name "Net-(IC11-VCAP1)") (class "Default")
      (node (ref "C17") (pin "2") (pinfunction "2_2") (pintype "passive"))
      (node (ref "IC11") (pin "28") (pinfunction "VCAP1_28") (pintype "passive"))
    )
    (net (code "97") (name "Net-(IC11-VCAP2)") (class "Default")
      (node (ref "C15") (pin "2") (pinfunction "2_2") (pintype "passive"))
      (node (ref "IC11") (pin "30") (pinfunction "VCAP2_30") (pintype "passive"))
    )
    (net (code "98") (name "Net-(IC11-VCAP3)") (class "Default")
      (node (ref "C13") (pin "2") (pinfunction "2_2") (pintype "passive"))
      (node (ref "C14") (pin "1") (pinfunction "1_1") (pintype "passive"))
      (node (ref "IC11") (pin "55") (pinfunction "VCAP3_55") (pintype "passive"))
    )
    (net (code "99") (name "Net-(IC11-VCAP4)") (class "Default")
      (node (ref "C11") (pin "2") (pinfunction "2_2") (pintype "passive"))
      (node (ref "IC11") (pin "26") (pinfunction "VCAP4_26") (pintype "output"))
    )
    (net (code "100") (name "Net-(IC11-~{PWDN})") (class "Default")
      (node (ref "IC11") (pin "35") (pinfunction "~{PWDN}_35") (pintype "power_in"))
      (node (ref "R51") (pin "1") (pinfunction "1_1") (pintype "passive"))
    )
    (net (code "101") (name "Net-(IC12-EN)") (class "Default")
      (node (ref "C21") (pin "1") (pinfunction "1_1") (pintype "passive"))
      (node (ref "IC12") (pin "1") (pinfunction "IN_1") (pintype "input"))
      (node (ref "IC12") (pin "3") (pinfunction "EN_3") (pintype "input"))
      (node (ref "L3") (pin "P$1") (pinfunction "1_P$1") (pintype "passive"))
    )
    (net (code "102") (name "Net-(IC13-EN)") (class "Default")
      (node (ref "C22") (pin "1") (pinfunction "1_1") (pintype "passive"))
      (node (ref "IC13") (pin "2") (pinfunction "IN_2") (pintype "input"))
      (node (ref "IC13") (pin "3") (pinfunction "EN_3") (pintype "input"))
      (node (ref "L4") (pin "P$1") (pinfunction "1_P$1") (pintype "passive"))
    )
    (net (code "103") (name "Net-(ISEL1A_1B-COM)") (class "Default")
      (node (ref "F3") (pin "1") (pinfunction "1_1") (pintype "passive"))
      (node (ref "ISEL1A_1") (pin "4") (pinfunction "COM_4") (pintype "passive"))
      (node (ref "ISEL1A_1") (pin "9") (pinfunction "COM_9") (pintype "passive"))
    )
    (net (code "104") (name "Net-(ISEL1A_2B-COM)") (class "Default")
      (node (ref "F5") (pin "1") (pinfunction "1_1") (pintype "passive"))
      (node (ref "ISEL1A_2") (pin "4") (pinfunction "COM_4") (pintype "passive"))
      (node (ref "ISEL1A_2") (pin "9") (pinfunction "COM_9") (pintype "passive"))
    )
    (net (code "105") (name "Net-(ISEL10A_1B-COM)") (class "Default")
      (node (ref "F4") (pin "1") (pinfunction "1_1") (pintype "passive"))
      (node (ref "ISEL10A_1") (pin "11") (pinfunction "COM_11") (pintype "passive"))
      (node (ref "ISEL10A_1") (pin "21") (pinfunction "COM_21") (pintype "passive"))
    )
    (net (code "106") (name "Net-(ISEL10A_1B-NC)") (class "Default")
      (node (ref "ISEL10A_1") (pin "12") (pinfunction "NC_12") (pintype "passive"))
      (node (ref "ISEL10A_1") (pin "22") (pinfunction "NC_22") (pintype "passive"))
      (node (ref "R36") (pin "2") (pinfunction "2_2") (pintype "passive"))
    )
    (net (code "107") (name "Net-(ISEL10A_2B-NC)") (class "Default")
      (node (ref "F6") (pin "1") (pinfunction "1_1") (pintype "passive"))
      (node (ref "ISEL10A_2") (pin "12") (pinfunction "NC_12") (pintype "passive"))
      (node (ref "ISEL10A_2") (pin "22") (pinfunction "NC_22") (pintype "passive"))
    )
    (net (code "108") (name "Net-(JP5-PadCOM)") (class "Default")
      (node (ref "JP5") (pin "COM") (pinfunction "COM_COM") (pintype "passive"))
      (node (ref "R52") (pin "2") (pinfunction "2_2") (pintype "passive"))
    )
    (net (code "109") (name "Net-(L1-1)") (class "Default")
      (node (ref "L1") (pin "P$1") (pinfunction "1_P$1") (pintype "passive"))
      (node (ref "R12") (pin "2") (pinfunction "2_2") (pintype "passive"))
      (node (ref "R8") (pin "2") (pinfunction "2_2") (pintype "passive"))
    )
    (net (code "110") (name "Net-(L2-1)") (class "Default")
      (node (ref "L2") (pin "P$1") (pinfunction "1_P$1") (pintype "passive"))
      (node (ref "R22") (pin "2") (pinfunction "2_2") (pintype "passive"))
      (node (ref "R25") (pin "2") (pinfunction "2_2") (pintype "passive"))
    )
    (net (code "111") (name "Net-(OK1-A)") (class "Default")
      (node (ref "OK1") (pin "1") (pinfunction "A_1") (pintype "passive"))
      (node (ref "R3") (pin "1") (pinfunction "1_1") (pintype "passive"))
    )
    (net (code "112") (name "Net-(OK1-S2)") (class "Default")
      (node (ref "OK1") (pin "3") (pinfunction "S2_3") (pintype "passive"))
      (node (ref "Q1") (pin "2") (pinfunction "D_2") (pintype "passive"))
      (node (ref "Q1") (pin "4") (pinfunction "D_4") (pintype "passive"))
    )
    (net (code "113") (name "Net-(OK2-A)") (class "Default")
      (node (ref "OK2") (pin "1") (pinfunction "A_1") (pintype "passive"))
      (node (ref "R6") (pin "2") (pinfunction "2_2") (pintype "passive"))
    )
    (net (code "114") (name "Net-(OK2-S2)") (class "Default")
      (node (ref "OK2") (pin "3") (pinfunction "S2_3") (pintype "passive"))
      (node (ref "R9") (pin "1") (pinfunction "1_1") (pintype "passive"))
    )
    (net (code "115") (name "Net-(OK3-A)") (class "Default")
      (node (ref "OK3") (pin "1") (pinfunction "A_1") (pintype "passive"))
      (node (ref "R19") (pin "1") (pinfunction "1_1") (pintype "passive"))
    )
    (net (code "116") (name "Net-(OK3-S2)") (class "Default")
      (node (ref "OK3") (pin "3") (pinfunction "S2_3") (pintype "passive"))
      (node (ref "Q3") (pin "2") (pinfunction "D_2") (pintype "passive"))
      (node (ref "Q3") (pin "4") (pinfunction "D_4") (pintype "passive"))
    )
    (net (code "117") (name "Net-(OK4-A)") (class "Default")
      (node (ref "OK4") (pin "1") (pinfunction "A_1") (pintype "passive"))
      (node (ref "R21") (pin "2") (pinfunction "2_2") (pintype "passive"))
    )
    (net (code "118") (name "Net-(OK4-S2)") (class "Default")
      (node (ref "OK4") (pin "3") (pinfunction "S2_3") (pintype "passive"))
      (node (ref "R23") (pin "1") (pinfunction "1_1") (pintype "passive"))
    )
    (net (code "119") (name "Net-(Q1-S)") (class "Default")
      (node (ref "Q1") (pin "3") (pinfunction "S_3") (pintype "passive"))
      (node (ref "Q2") (pin "1") (pinfunction "G_1") (pintype "passive"))
      (node (ref "R1") (pin "2") (pinfunction "2_2") (pintype "passive"))
    )
    (net (code "120") (name "Net-(Q3-S)") (class "Default")
      (node (ref "Q3") (pin "3") (pinfunction "S_3") (pintype "passive"))
      (node (ref "Q4") (pin "1") (pinfunction "G_1") (pintype "passive"))
      (node (ref "R18") (pin "2") (pinfunction "2_2") (pintype "passive"))
    )
    (net (code "121") (name "Net-(Q5-D)") (class "Default")
      (node (ref "Q5") (pin "3") (pinfunction "D_3") (pintype "passive"))
      (node (ref "Q6") (pin "3") (pinfunction "D_3") (pintype "passive"))
    )
    (net (code "122") (name "Net-(Q6-S)") (class "Default")
      (node (ref "Q6") (pin "2") (pinfunction "S_2") (pintype "passive"))
      (node (ref "R31") (pin "1") (pinfunction "1_1") (pintype "passive"))
      (node (ref "R33") (pin "2") (pinfunction "2_2") (pintype "passive"))
    )
    (net (code "123") (name "Net-(Q7-D)") (class "Default")
      (node (ref "Q7") (pin "3") (pinfunction "D_3") (pintype "passive"))
      (node (ref "Q8") (pin "3") (pinfunction "D_3") (pintype "passive"))
    )
    (net (code "124") (name "Net-(Q8-S)") (class "Default")
      (node (ref "Q8") (pin "2") (pinfunction "S_2") (pintype "passive"))
      (node (ref "R41") (pin "1") (pinfunction "1_1") (pintype "passive"))
      (node (ref "R43") (pin "2") (pinfunction "2_2") (pintype "passive"))
    )
    (net (code "125") (name "Net-(R8-Pad1)") (class "Default")
      (node (ref "R8") (pin "1") (pinfunction "1_1") (pintype "passive"))
      (node (ref "R9") (pin "2") (pinfunction "2_2") (pintype "passive"))
    )
    (net (code "126") (name "Net-(R12-Pad1)") (class "Default")
      (node (ref "R12") (pin "1") (pinfunction "1_1") (pintype "passive"))
      (node (ref "R13") (pin "2") (pinfunction "2_2") (pintype "passive"))
    )
    (net (code "127") (name "Net-(R13-Pad1)") (class "Default")
      (node (ref "R13") (pin "1") (pinfunction "1_1") (pintype "passive"))
      (node (ref "R14") (pin "2") (pinfunction "2_2") (pintype "passive"))
    )
    (net (code "128") (name "Net-(R15-Pad1)") (class "Default")
      (node (ref "R15") (pin "1") (pinfunction "1_1") (pintype "passive"))
      (node (ref "R16") (pin "2") (pinfunction "2_2") (pintype "passive"))
    )
    (net (code "129") (name "Net-(R22-Pad1)") (class "Default")
      (node (ref "R22") (pin "1") (pinfunction "1_1") (pintype "passive"))
      (node (ref "R23") (pin "2") (pinfunction "2_2") (pintype "passive"))
    )
    (net (code "130") (name "Net-(R25-Pad1)") (class "Default")
      (node (ref "R25") (pin "1") (pinfunction "1_1") (pintype "passive"))
      (node (ref "R26") (pin "2") (pinfunction "2_2") (pintype "passive"))
    )
    (net (code "131") (name "Net-(R26-Pad1)") (class "Default")
      (node (ref "R26") (pin "1") (pinfunction "1_1") (pintype "passive"))
      (node (ref "R27") (pin "2") (pinfunction "2_2") (pintype "passive"))
    )
    (net (code "132") (name "Net-(R28-Pad1)") (class "Default")
      (node (ref "R28") (pin "1") (pinfunction "1_1") (pintype "passive"))
      (node (ref "R29") (pin "2") (pinfunction "2_2") (pintype "passive"))
    )
    (net (code "133") (name "Net-(R33-Pad1)") (class "Default")
      (node (ref "R33") (pin "1") (pinfunction "1_1") (pintype "passive"))
      (node (ref "R33") (pin "1S") (pinfunction "1S_1S") (pintype "passive"))
      (node (ref "R36") (pin "2S") (pinfunction "2S_2S") (pintype "passive"))
    )
    (net (code "134") (name "Net-(R38-Pad1)") (class "Default")
      (node (ref "R38") (pin "1") (pinfunction "1_1") (pintype "passive"))
      (node (ref "R39") (pin "2") (pinfunction "2_2") (pintype "passive"))
    )
    (net (code "135") (name "Net-(R43-Pad1)") (class "Default")
      (node (ref "R43") (pin "1") (pinfunction "1_1") (pintype "passive"))
      (node (ref "R43") (pin "1S") (pinfunction "1S_1S") (pintype "passive"))
      (node (ref "R46") (pin "2S") (pinfunction "2S_2S") (pintype "passive"))
    )
    (net (code "136") (name "Net-(R48-Pad1)") (class "Default")
      (node (ref "R48") (pin "1") (pinfunction "1_1") (pintype "passive"))
      (node (ref "R49") (pin "2") (pinfunction "2_2") (pintype "passive"))
    )
    (net (code "137") (name "Net-(XO1-OUT)") (class "Default")
      (node (ref "JP6") (pin "NC") (pinfunction "NC_NC") (pintype "passive"))
      (node (ref "XO1") (pin "4") (pinfunction "OUT_4") (pintype "output"))
    )
    (net (code "138") (name "USEL1#1") (class "Default")
      (node (ref "IC2") (pin "8") (pinfunction "IN_8") (pintype "input"))
      (node (ref "R6") (pin "1") (pinfunction "1_1") (pintype "passive"))
      (node (ref "X3") (pin "5") (pinfunction "1_5") (pintype "passive"))
    )
    (net (code "139") (name "USEL1#2") (class "Default")
      (node (ref "IC5") (pin "8") (pinfunction "IN_8") (pintype "input"))
      (node (ref "R21") (pin "1") (pinfunction "1_1") (pintype "passive"))
      (node (ref "X3") (pin "6") (pinfunction "1_6") (pintype "passive"))
    )
    (net (code "140") (name "USEL1#3") (class "Default")
      (node (ref "IC7") (pin "8") (pinfunction "IN_8") (pintype "input"))
      (node (ref "X3") (pin "11") (pinfunction "1_11") (pintype "passive"))
    )
    (net (code "141") (name "USEL1#4") (class "Default")
      (node (ref "IC9") (pin "8") (pinfunction "IN_8") (pintype "input"))
      (node (ref "X3") (pin "12") (pinfunction "1_12") (pintype "passive"))
    )
    (net (code "142") (name "USEL10#1") (class "Default")
      (node (ref "IC2") (pin "1") (pinfunction "IN_1") (pintype "input"))
      (node (ref "X3") (pin "7") (pinfunction "1_7") (pintype "passive"))
    )
    (net (code "143") (name "USEL10#2") (class "Default")
      (node (ref "IC5") (pin "1") (pinfunction "IN_1") (pintype "input"))
      (node (ref "X3") (pin "8") (pinfunction "1_8") (pintype "passive"))
    )
    (net (code "144") (name "USEL10#3") (class "Default")
      (node (ref "IC7") (pin "1") (pinfunction "IN_1") (pintype "input"))
      (node (ref "X3") (pin "13") (pinfunction "1_13") (pintype "passive"))
    )
    (net (code "145") (name "USEL10#4") (class "Default")
      (node (ref "IC9") (pin "1") (pinfunction "IN_1") (pintype "input"))
      (node (ref "X3") (pin "14") (pinfunction "1_14") (pintype "passive"))
    )
    (net (code "146") (name "USEL100#1") (class "Default")
      (node (ref "IC2") (pin "16") (pinfunction "IN_16") (pintype "input"))
      (node (ref "X3") (pin "9") (pinfunction "1_9") (pintype "passive"))
    )
    (net (code "147") (name "USEL100#2") (class "Default")
      (node (ref "IC5") (pin "16") (pinfunction "IN_16") (pintype "input"))
      (node (ref "X3") (pin "10") (pinfunction "1_10") (pintype "passive"))
    )
    (net (code "148") (name "unconnected-(IC11-GPIO1-Pad42)") (class "Default")
      (node (ref "IC11") (pin "42") (pinfunction "GPIO1_42") (pintype "bidirectional"))
    )
    (net (code "149") (name "unconnected-(IC11-GPIO2-Pad44)") (class "Default")
      (node (ref "IC11") (pin "44") (pinfunction "GPIO2_44") (pintype "bidirectional"))
    )
    (net (code "150") (name "unconnected-(IC11-GPIO3-Pad45)") (class "Default")
      (node (ref "IC11") (pin "45") (pinfunction "GPIO3_45") (pintype "bidirectional"))
    )
    (net (code "151") (name "unconnected-(IC11-GPIO4-Pad46)") (class "Default")
      (node (ref "IC11") (pin "46") (pinfunction "GPIO4_46") (pintype "bidirectional"))
    )
    (net (code "152") (name "unconnected-(IC11-IN5N(NC)-Pad7)") (class "Default")
      (node (ref "IC11") (pin "7") (pinfunction "IN5N(NC)_7") (pintype "input"))
    )
    (net (code "153") (name "unconnected-(IC11-IN5P(NC)-Pad8)") (class "Default")
      (node (ref "IC11") (pin "8") (pinfunction "IN5P(NC)_8") (pintype "input"))
    )
    (net (code "154") (name "unconnected-(IC11-IN6N(NC)-Pad5)") (class "Default")
      (node (ref "IC11") (pin "5") (pinfunction "IN6N(NC)_5") (pintype "input"))
    )
    (net (code "155") (name "unconnected-(IC11-IN6P(NC)-Pad6)") (class "Default")
      (node (ref "IC11") (pin "6") (pinfunction "IN6P(NC)_6") (pintype "input"))
    )
    (net (code "156") (name "unconnected-(IC11-IN7N(NC)-Pad3)") (class "Default")
      (node (ref "IC11") (pin "3") (pinfunction "IN7N(NC)_3") (pintype "input"))
    )
    (net (code "157") (name "unconnected-(IC11-IN7P(NC)-Pad4)") (class "Default")
      (node (ref "IC11") (pin "4") (pinfunction "IN7P(NC)_4") (pintype "input"))
    )
    (net (code "158") (name "unconnected-(IC11-IN8N(NC)-Pad1)") (class "Default")
      (node (ref "IC11") (pin "1") (pinfunction "IN8N(NC)_1") (pintype "input"))
    )
    (net (code "159") (name "unconnected-(IC11-IN8P(NC)-Pad2)") (class "Default")
      (node (ref "IC11") (pin "2") (pinfunction "IN8P(NC)_2") (pintype "input"))
    )
    (net (code "160") (name "unconnected-(IC11-OPAMPN-Pad61)") (class "Default")
      (node (ref "IC11") (pin "61") (pinfunction "OPAMPN_61") (pintype "input"))
    )
    (net (code "161") (name "unconnected-(IC11-OPAMPOUT-Pad63)") (class "Default")
      (node (ref "IC11") (pin "63") (pinfunction "OPAMPOUT_63") (pintype "output"))
    )
    (net (code "162") (name "unconnected-(IC11-OPAMPP-Pad60)") (class "Default")
      (node (ref "IC11") (pin "60") (pinfunction "OPAMPP_60") (pintype "input"))
    )
    (net (code "163") (name "unconnected-(IC11-TESTN-Pad18)") (class "Default")
      (node (ref "IC11") (pin "18") (pinfunction "TESTN_18") (pintype "bidirectional"))
    )
    (net (code "164") (name "unconnected-(IC11-TESTP-Pad17)") (class "Default")
      (node (ref "IC11") (pin "17") (pinfunction "TESTP_17") (pintype "bidirectional"))
    )
    (net (code "165") (name "unconnected-(IC12-NR-Pad4)") (class "Default")
      (node (ref "IC12") (pin "4") (pinfunction "NR_4") (pintype "passive"))
    )
    (net (code "166") (name "unconnected-(IC13-NR-Pad4)") (class "Default")
      (node (ref "IC13") (pin "4") (pinfunction "NR_4") (pintype "passive"))
    )
    (net (code "167") (name "unconnected-(ISEL10A_1B-NO-Pad14)") (class "Default")
      (node (ref "ISEL10A_1") (pin "14") (pinfunction "NO_14") (pintype "passive"))
    )
    (net (code "168") (name "unconnected-(ISEL10A_1C-NO-Pad24)") (class "Default")
      (node (ref "ISEL10A_1") (pin "24") (pinfunction "NO_24") (pintype "passive"))
    )
    (net (code "169") (name "unconnected-(ISEL10A_2B-NO-Pad14)") (class "Default")
      (node (ref "ISEL10A_2") (pin "14") (pinfunction "NO_14") (pintype "passive"))
    )
    (net (code "170") (name "unconnected-(ISEL10A_2C-NO-Pad24)") (class "Default")
      (node (ref "ISEL10A_2") (pin "24") (pinfunction "NO_24") (pintype "passive"))
    )
    (net (code "171") (name "unconnected-(X2I-1-Pad17)") (class "Default")
      (node (ref "X2") (pin "17") (pinfunction "1_17") (pintype "passive"))
    )
    (net (code "172") (name "unconnected-(X2J-1-Pad18)") (class "Default")
      (node (ref "X2") (pin "18") (pinfunction "1_18") (pintype "passive"))
    )
    (net (code "173") (name "unconnected-(XO1-EN-Pad1)") (class "Default")
      (node (ref "XO1") (pin "1") (pinfunction "EN_1") (pintype "input"))
    )
    (net (code "174") (name "~{ADC_CS}") (class "Default")
      (node (ref "IC11") (pin "39") (pinfunction "~{CS}_39") (pintype "input"))
      (node (ref "X2") (pin "5") (pinfunction "1_5") (pintype "passive"))
    )
    (net (code "175") (name "~{ADC_DRDY}") (class "Default")
      (node (ref "IC11") (pin "47") (pinfunction "~{DRDY}_47") (pintype "output"))
      (node (ref "X2") (pin "7") (pinfunction "1_7") (pintype "passive"))
    )
    (net (code "176") (name "~{RESET}") (class "Default")
      (node (ref "IC11") (pin "36") (pinfunction "~{RESET}_36") (pintype "input"))
      (node (ref "X2") (pin "9") (pinfunction "1_9") (pintype "passive"))
    )
  )
)
